# gd32.net
KiCad netlist of a schematic drawn in EAGLE
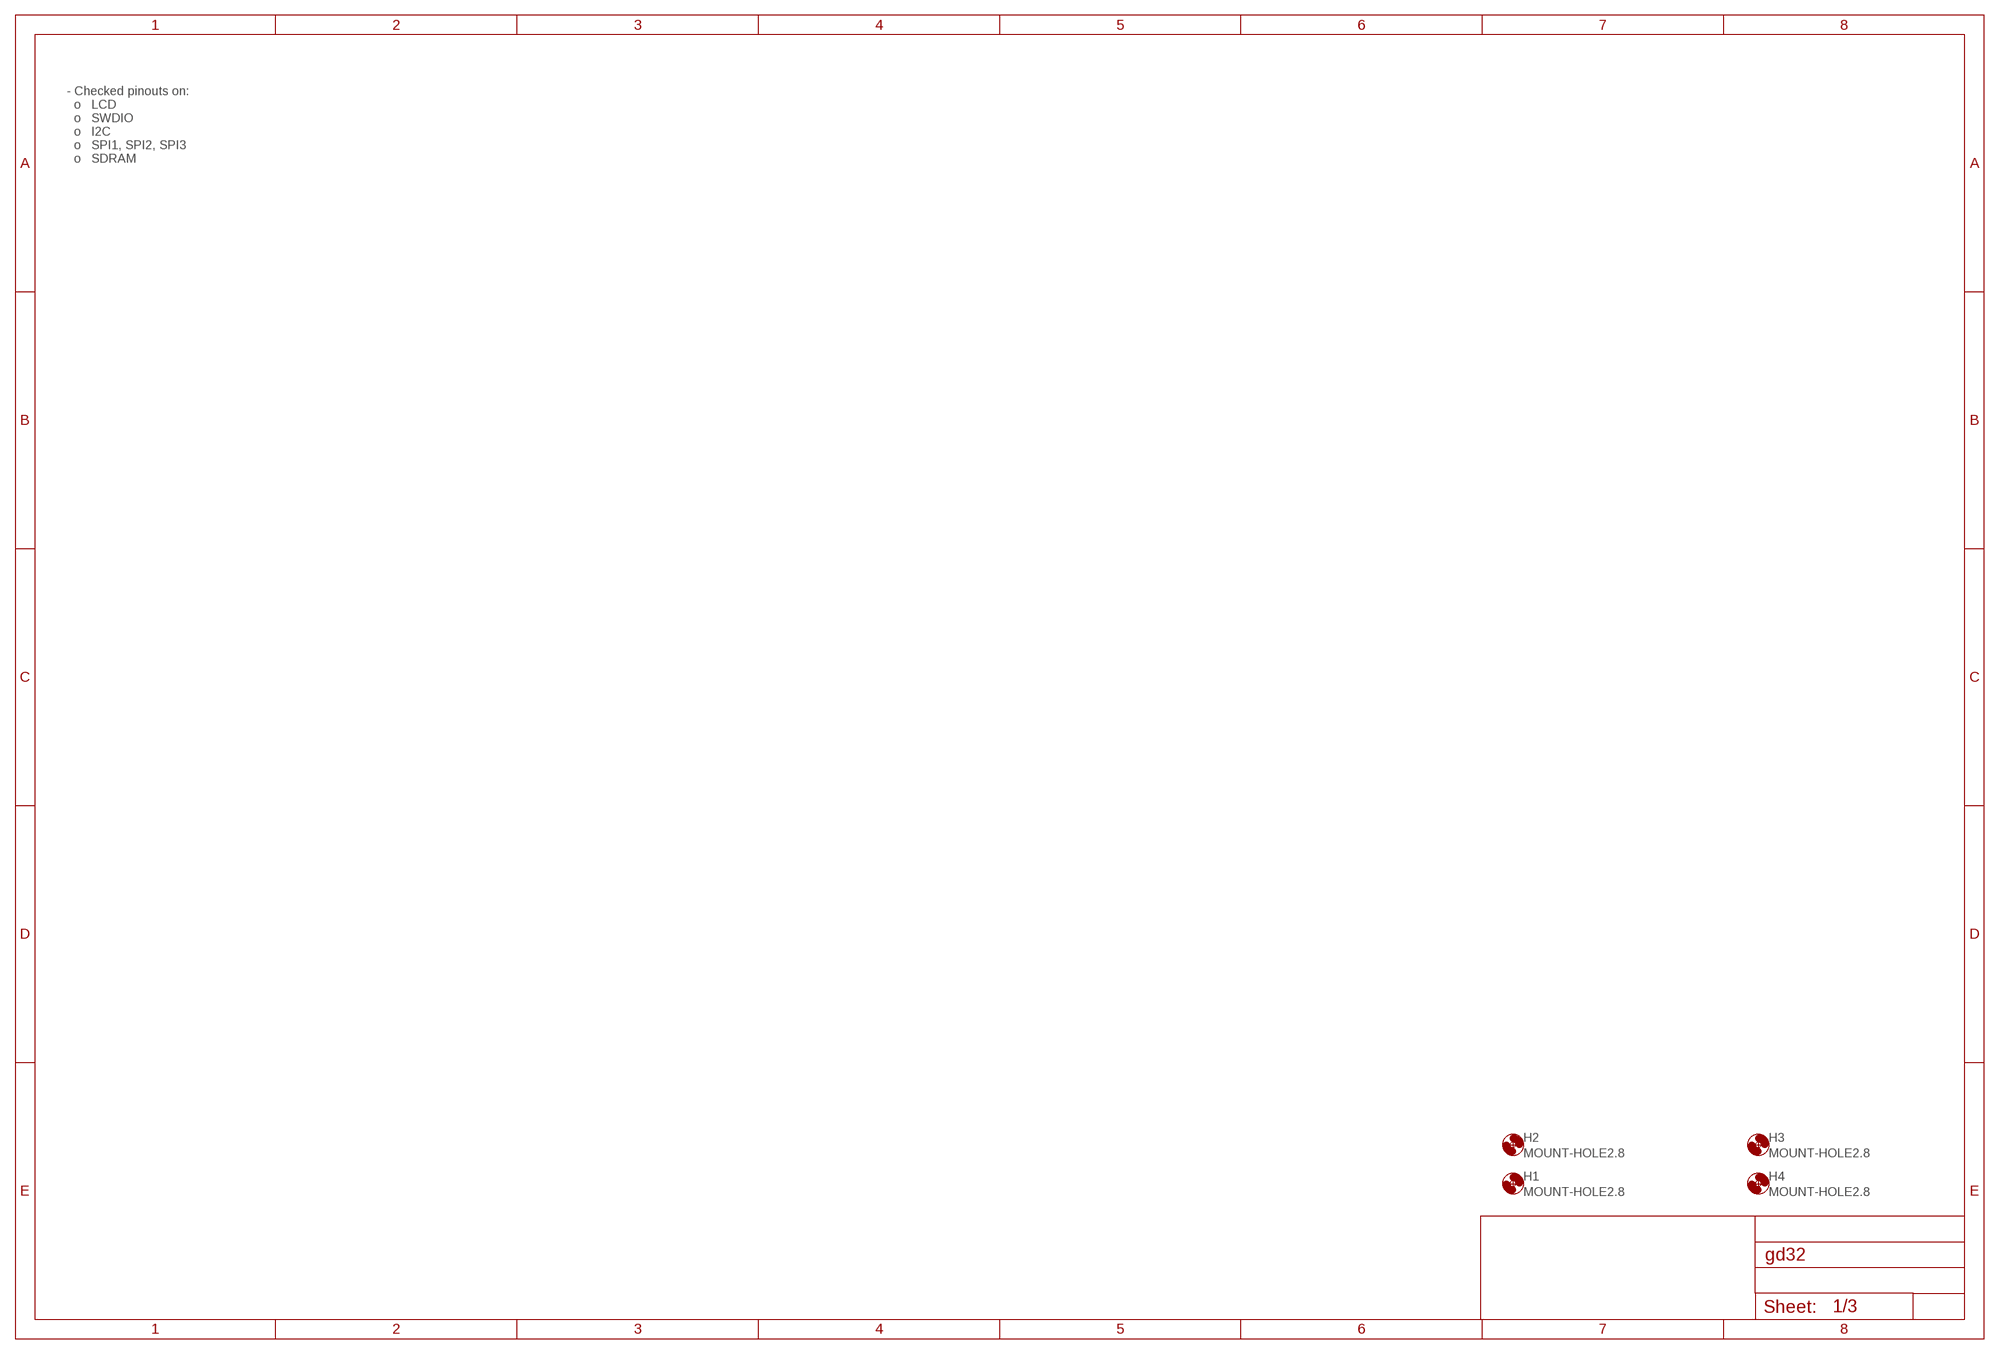
[diagram p0: schematic, sheet 1]
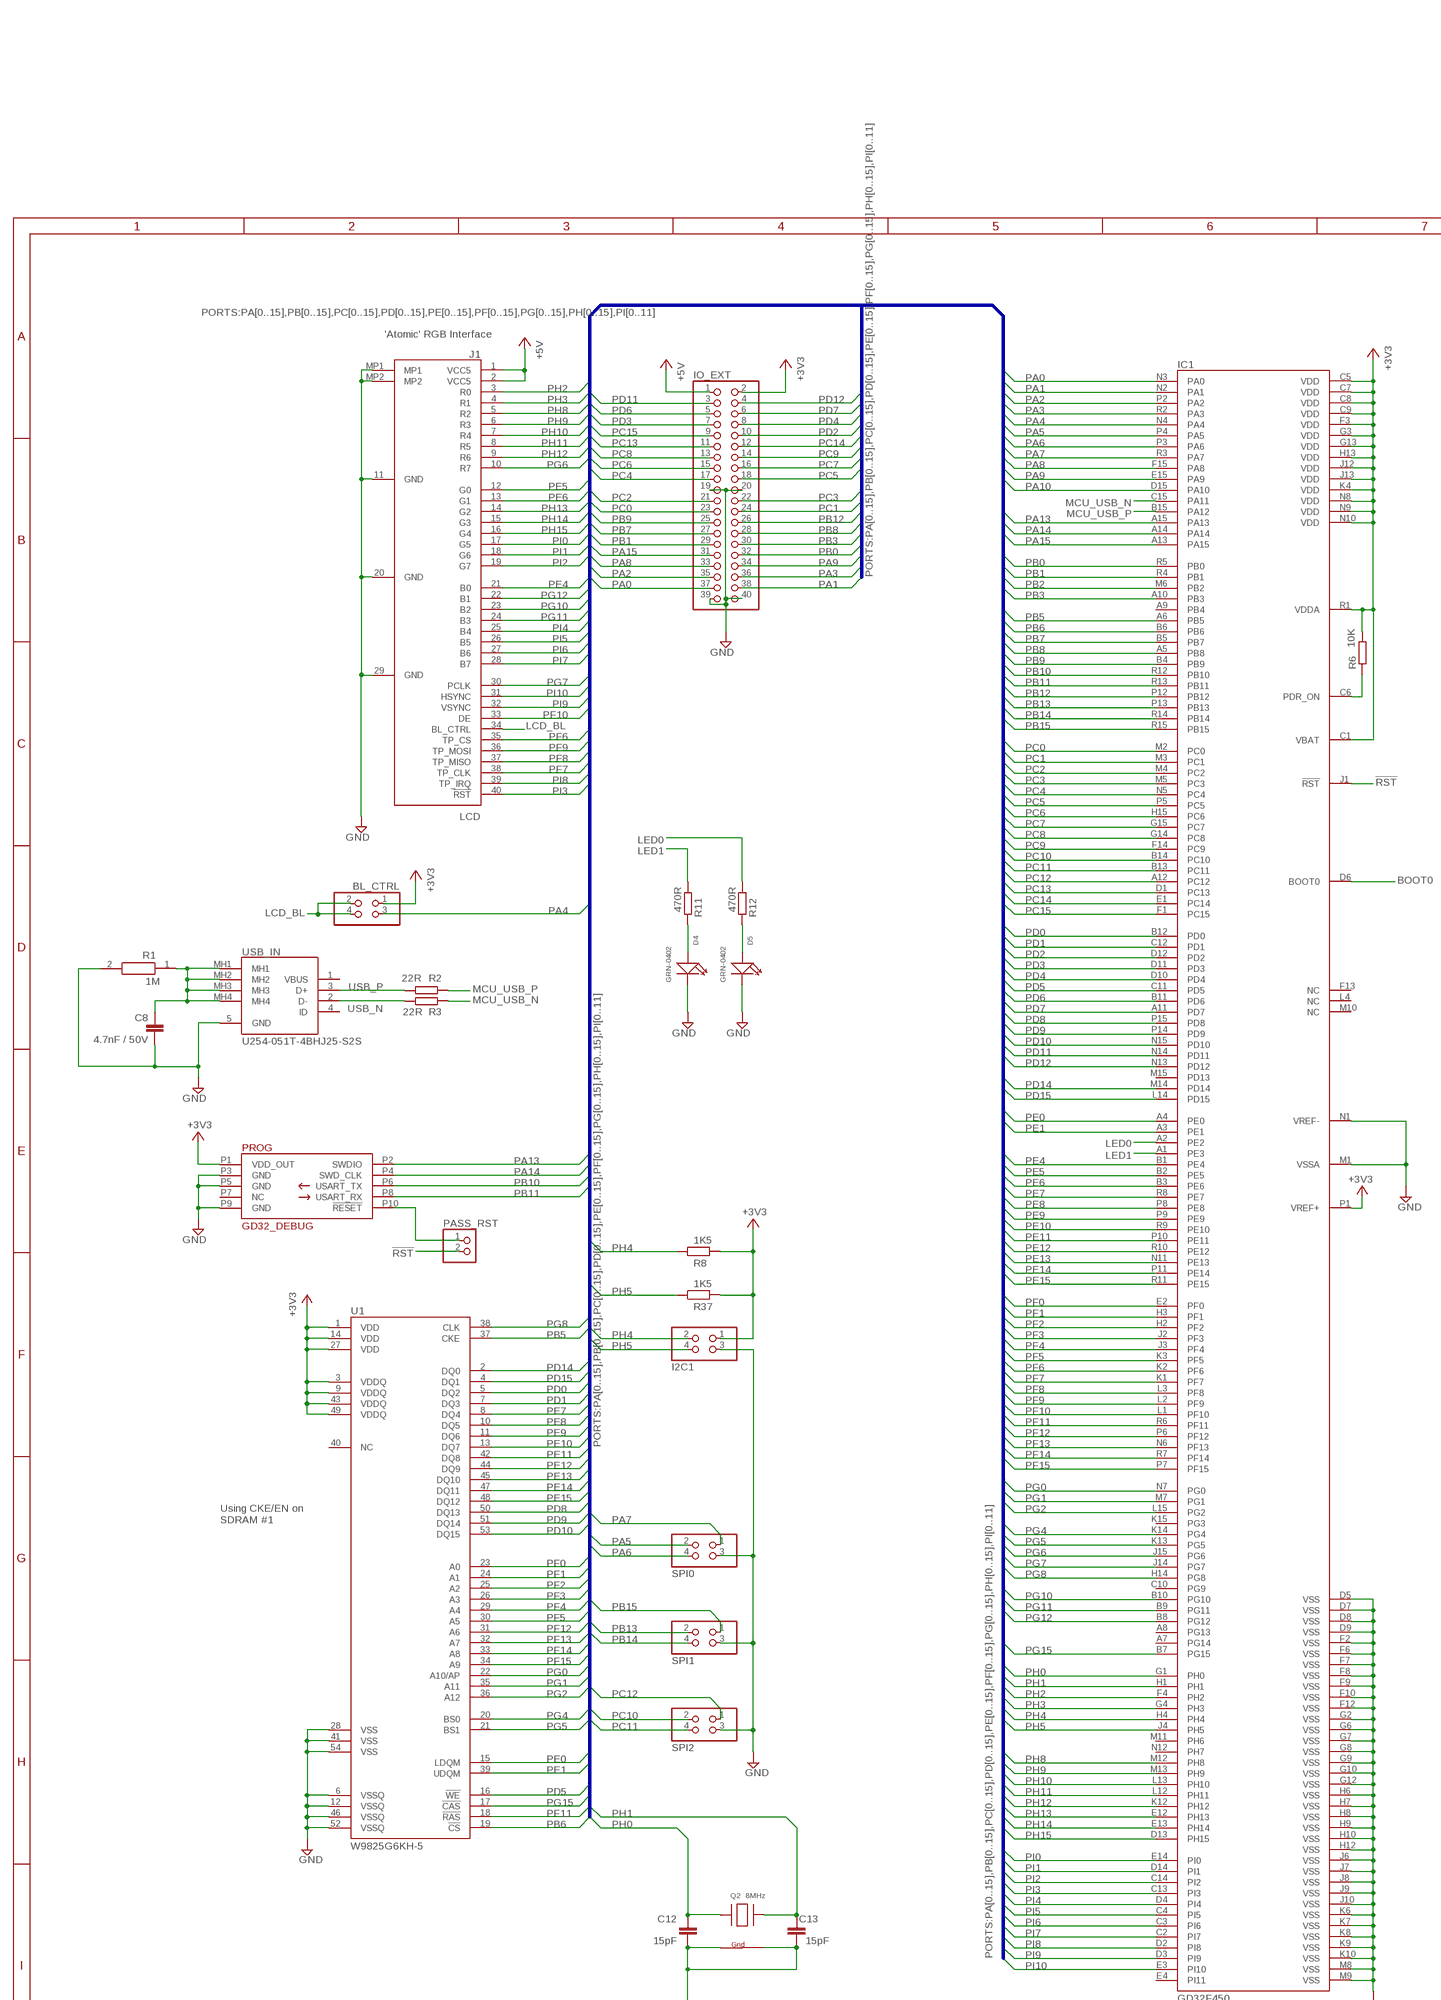
[diagram p1: schematic, sheet 2, part 1 of 3]
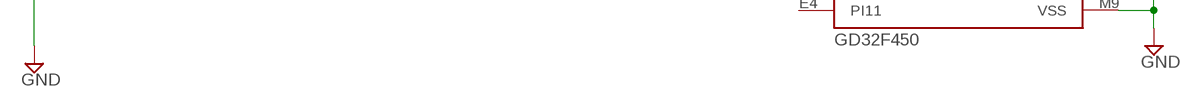
[diagram p2: schematic, sheet 2, part 2 of 3]
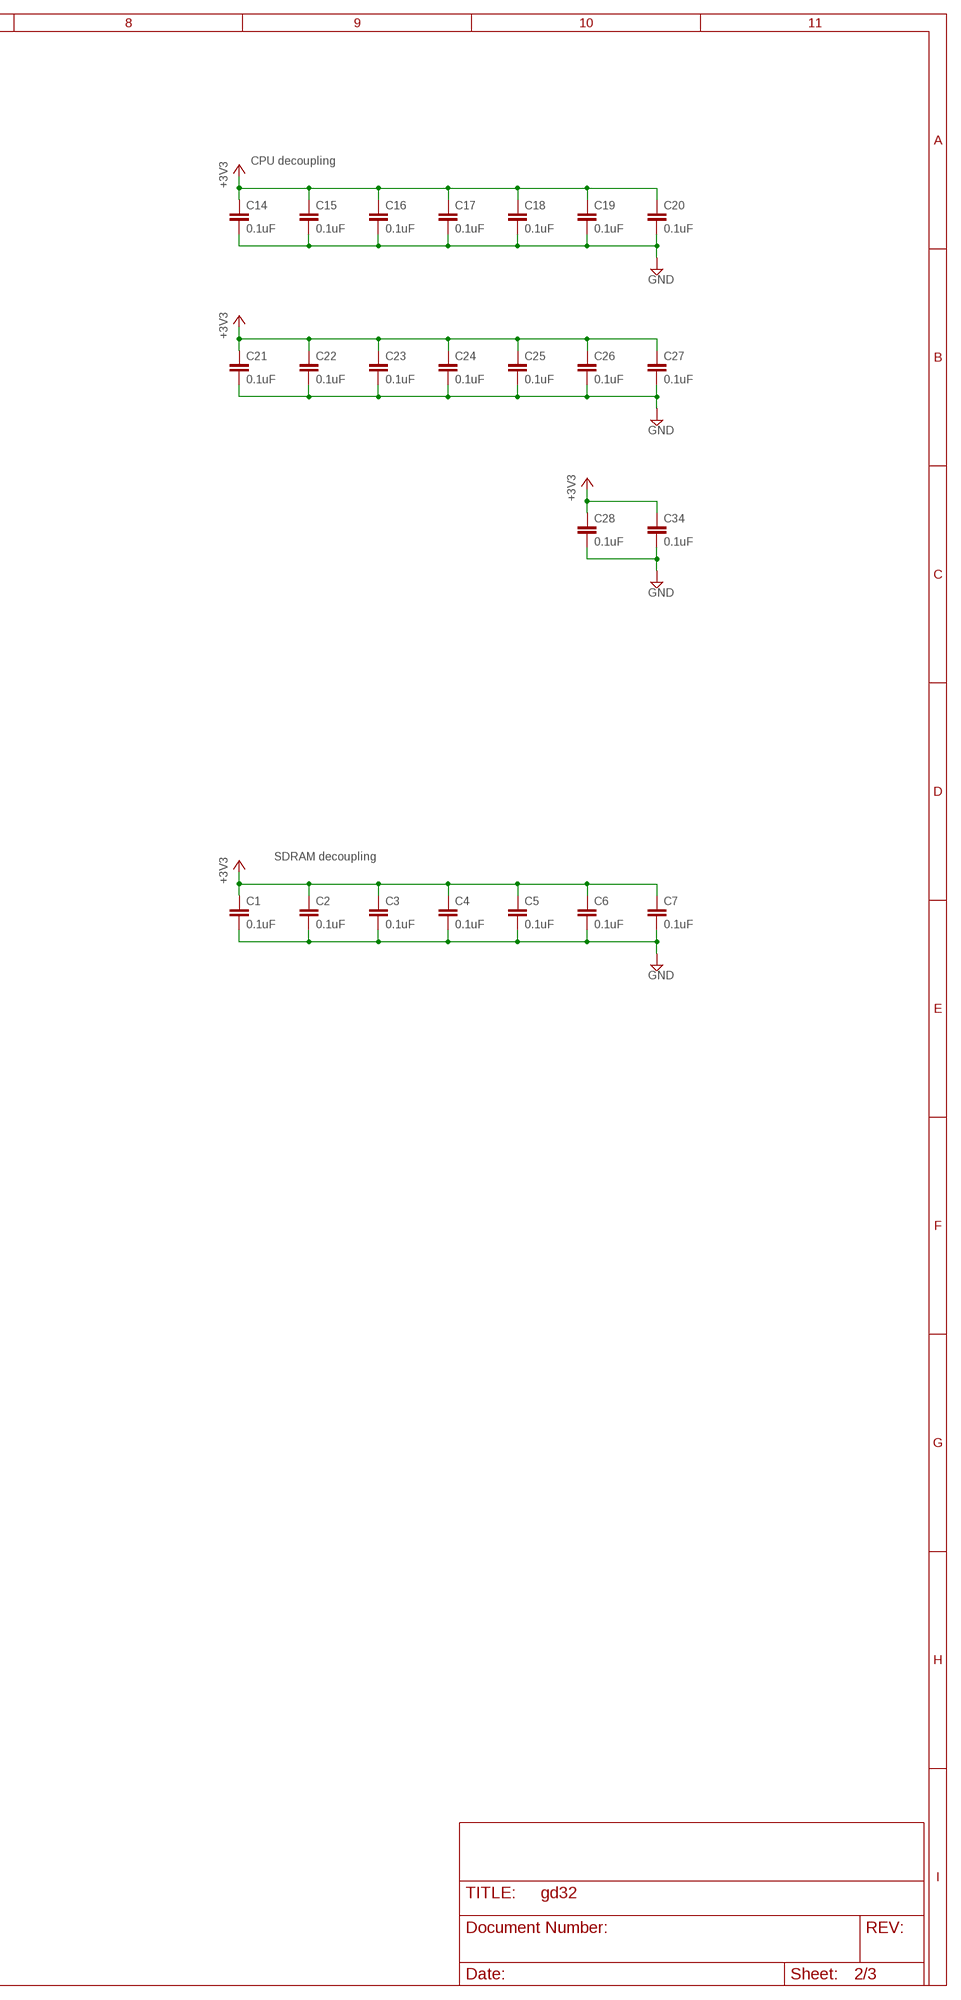
[diagram p3: schematic, sheet 2, part 3 of 3]
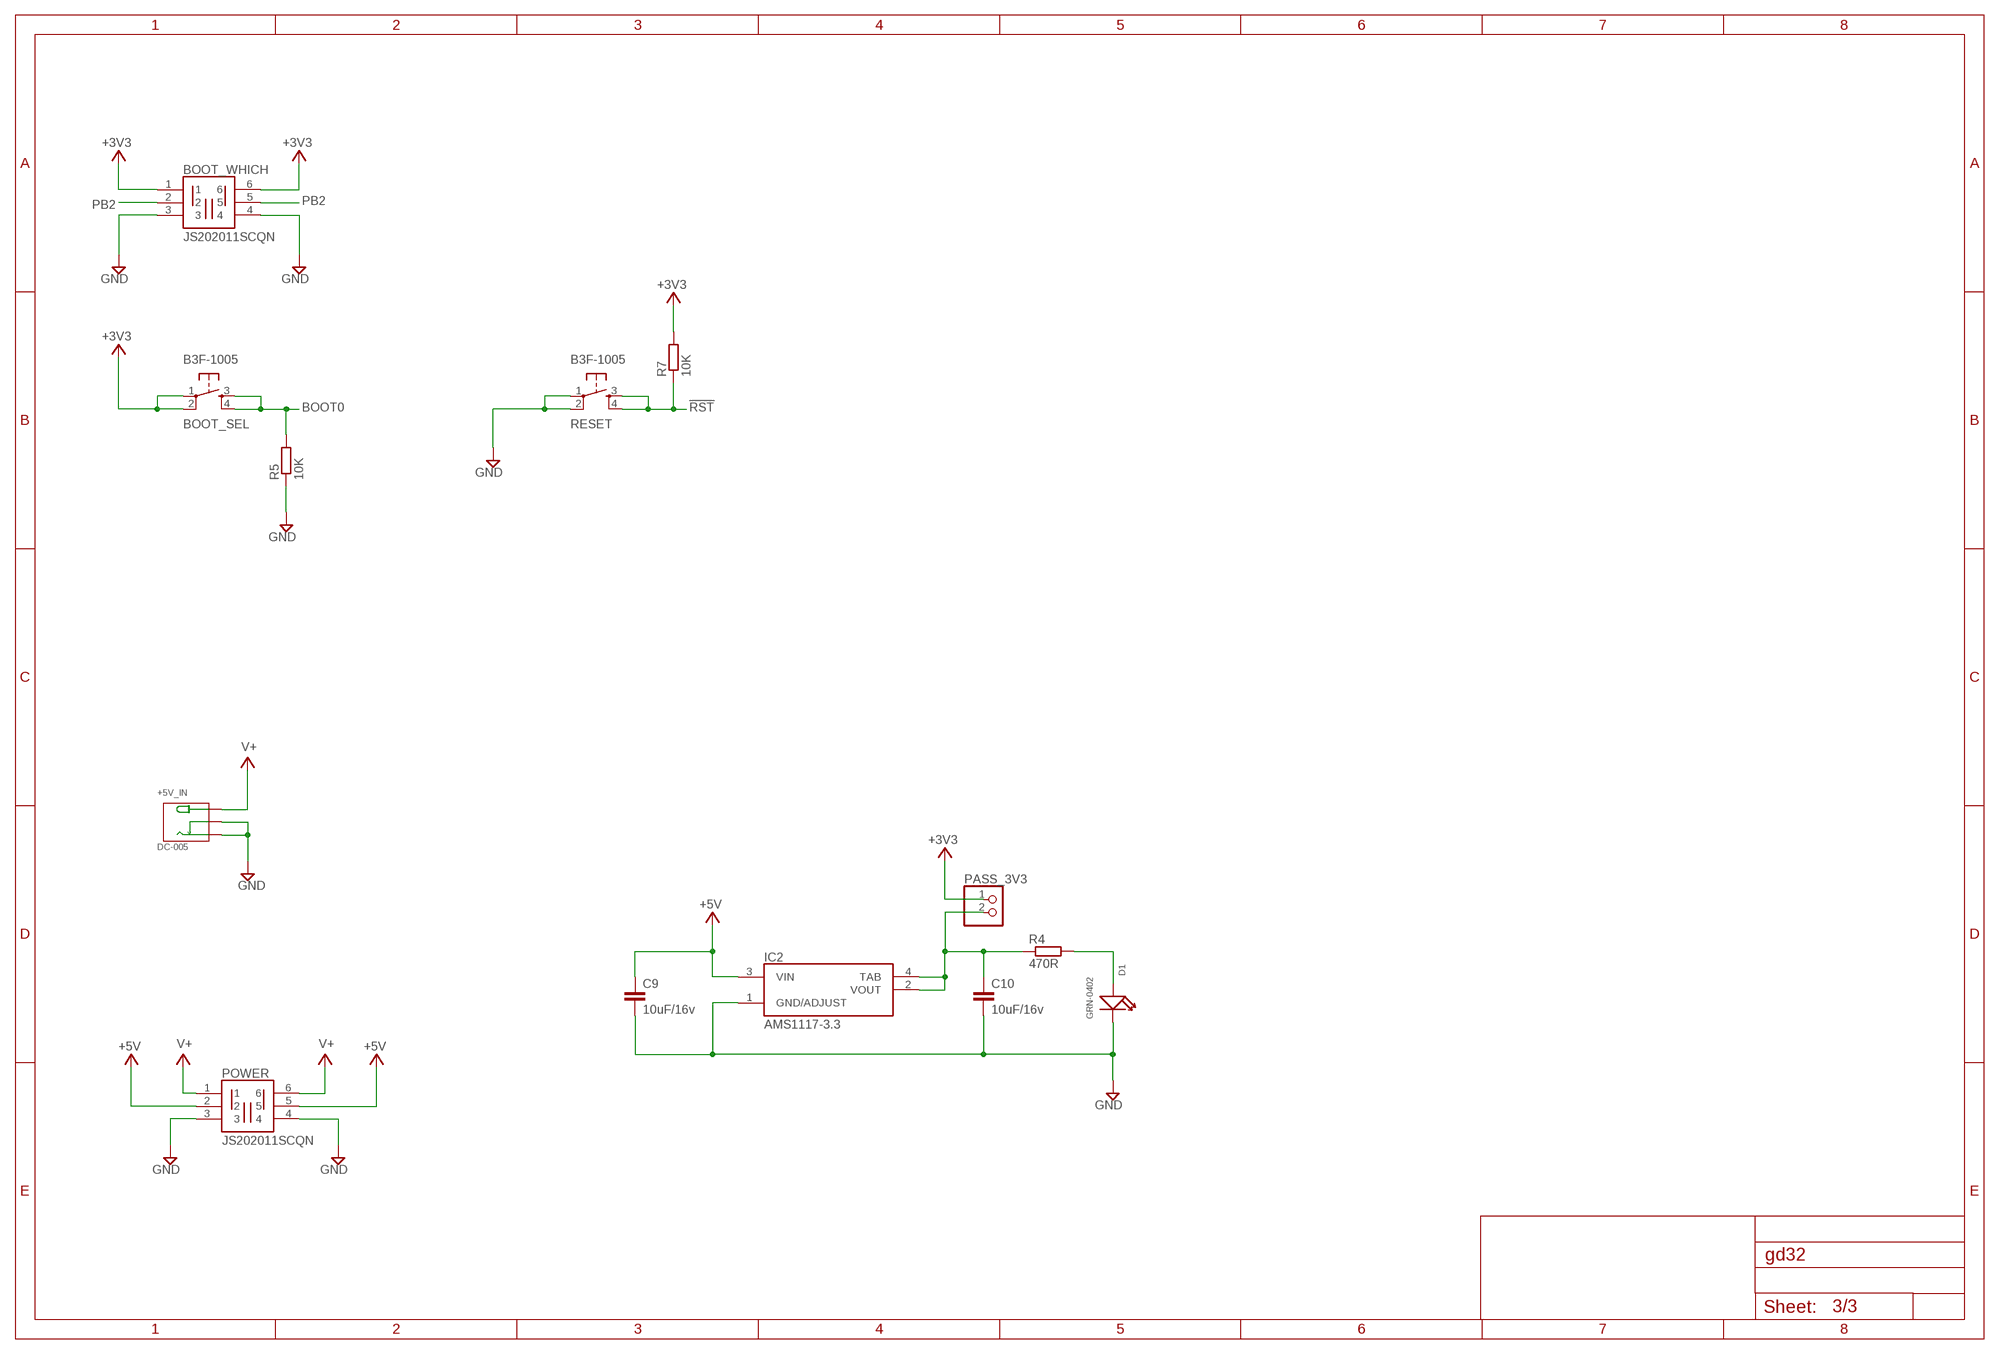
[diagram p4: schematic, sheet 3]

(export (version "E")
  (design (tool "Eeschema 10.0.6"))
  (components
    (comp (ref "+5V_IN")
      (value "DC-005")
      (footprint "eagle-import:DCJ3P-14.2X11.0X9.0MM")
      (libsource (lib "eagle-import") (part "CONN-POWER-JACK-2.1MM(DC-005)"))
    )
    (comp (ref "BOOT_SEL")
      (value "B3F-1005")
      (footprint "eagle-import:TACTILE-PTH")
      (fields (field (name "USE") "B3F-1005"))
      (libsource (lib "eagle-import") (part "TAC_SWITCHPTH"))
    )
    (comp (ref "BOOT_WHICH")
      (value "JS202011SCQN")
      (footprint "eagle-import:JS202011SCQN")
      (fields (field (name "MOUSER_PART_NUMBER") "611-JS202011SCQN"))
      (libsource (lib "eagle-import") (part "JS202011SCQN"))
    )
    (comp (ref "C9")
      (value "10uF/16v")
      (footprint "eagle-import:C0603")
      (libsource (lib "eagle-import") (part "C-EUC0603"))
    )
    (comp (ref "C10")
      (value "10uF/16v")
      (footprint "eagle-import:C0603")
      (libsource (lib "eagle-import") (part "C-EUC0603"))
    )
    (comp (ref "D1")
      (value "GRN-0402")
      (footprint "eagle-import:LED-0402")
      (fields (field (name "MPN") "BL-HB337A-AV-TRB"))
      (libsource (lib "eagle-import") (part "SMD-LED-CLEAR-BLUE(0402)"))
    )
    (comp (ref "IC2")
      (value "AMS1117-3.3")
      (footprint "eagle-import:SOT229P700X180-4N")
      (fields (field (name "MANUFACTURER_PART_NUMBER") "AMS1117-1.5"))
      (libsource (lib "eagle-import") (part "AMS1117-1.5"))
    )
    (comp (ref "PASS_3V3")
      (value "PINHD-1X2")
      (footprint "eagle-import:1X02")
      (libsource (lib "eagle-import") (part "PINHD-1X2"))
    )
    (comp (ref "POWER")
      (value "JS202011SCQN")
      (footprint "eagle-import:JS202011SCQN")
      (fields (field (name "MOUSER_PART_NUMBER") "611-JS202011SCQN"))
      (libsource (lib "eagle-import") (part "JS202011SCQN"))
    )
    (comp (ref "R4")
      (value "470R")
      (footprint "eagle-import:R0402")
      (libsource (lib "eagle-import") (part "R-EU_R0402"))
    )
    (comp (ref "R5")
      (value "10K")
      (footprint "eagle-import:R0402")
      (libsource (lib "eagle-import") (part "R-EU_R0402"))
    )
    (comp (ref "R7")
      (value "10K")
      (footprint "eagle-import:R0402")
      (libsource (lib "eagle-import") (part "R-EU_R0402"))
    )
    (comp (ref "RESET")
      (value "B3F-1005")
      (footprint "eagle-import:TACTILE-PTH")
      (fields (field (name "USE") "B3F-1005"))
      (libsource (lib "eagle-import") (part "TAC_SWITCHPTH"))
    )
    (comp (ref "BL_CTRL")
      (value "PINHD-2X2")
      (footprint "eagle-import:2X02")
      (libsource (lib "eagle-import") (part "PINHD-2X2"))
    )
    (comp (ref "C1")
      (value "0.1uF")
      (footprint "eagle-import:C0201")
      (libsource (lib "eagle-import") (part "C-EUC0201"))
    )
    (comp (ref "C2")
      (value "0.1uF")
      (footprint "eagle-import:C0201")
      (libsource (lib "eagle-import") (part "C-EUC0201"))
    )
    (comp (ref "C3")
      (value "0.1uF")
      (footprint "eagle-import:C0201")
      (libsource (lib "eagle-import") (part "C-EUC0201"))
    )
    (comp (ref "C4")
      (value "0.1uF")
      (footprint "eagle-import:C0201")
      (libsource (lib "eagle-import") (part "C-EUC0201"))
    )
    (comp (ref "C5")
      (value "0.1uF")
      (footprint "eagle-import:C0201")
      (libsource (lib "eagle-import") (part "C-EUC0201"))
    )
    (comp (ref "C6")
      (value "0.1uF")
      (footprint "eagle-import:C0201")
      (libsource (lib "eagle-import") (part "C-EUC0201"))
    )
    (comp (ref "C7")
      (value "0.1uF")
      (footprint "eagle-import:C0201")
      (libsource (lib "eagle-import") (part "C-EUC0201"))
    )
    (comp (ref "C8")
      (value "4.7nF / 50V")
      (footprint "eagle-import:C0201")
      (libsource (lib "eagle-import") (part "C-EUC0201"))
    )
    (comp (ref "C12")
      (value "15pF")
      (footprint "eagle-import:C0201")
      (libsource (lib "eagle-import") (part "C-EUC0201"))
    )
    (comp (ref "C13")
      (value "15pF")
      (footprint "eagle-import:C0201")
      (libsource (lib "eagle-import") (part "C-EUC0201"))
    )
    (comp (ref "C14")
      (value "0.1uF")
      (footprint "eagle-import:C0201")
      (libsource (lib "eagle-import") (part "C-EUC0201"))
    )
    (comp (ref "C15")
      (value "0.1uF")
      (footprint "eagle-import:C0201")
      (libsource (lib "eagle-import") (part "C-EUC0201"))
    )
    (comp (ref "C16")
      (value "0.1uF")
      (footprint "eagle-import:C0201")
      (libsource (lib "eagle-import") (part "C-EUC0201"))
    )
    (comp (ref "C17")
      (value "0.1uF")
      (footprint "eagle-import:C0201")
      (libsource (lib "eagle-import") (part "C-EUC0201"))
    )
    (comp (ref "C18")
      (value "0.1uF")
      (footprint "eagle-import:C0201")
      (libsource (lib "eagle-import") (part "C-EUC0201"))
    )
    (comp (ref "C19")
      (value "0.1uF")
      (footprint "eagle-import:C0201")
      (libsource (lib "eagle-import") (part "C-EUC0201"))
    )
    (comp (ref "C20")
      (value "0.1uF")
      (footprint "eagle-import:C0201")
      (libsource (lib "eagle-import") (part "C-EUC0201"))
    )
    (comp (ref "C21")
      (value "0.1uF")
      (footprint "eagle-import:C0201")
      (libsource (lib "eagle-import") (part "C-EUC0201"))
    )
    (comp (ref "C22")
      (value "0.1uF")
      (footprint "eagle-import:C0201")
      (libsource (lib "eagle-import") (part "C-EUC0201"))
    )
    (comp (ref "C23")
      (value "0.1uF")
      (footprint "eagle-import:C0201")
      (libsource (lib "eagle-import") (part "C-EUC0201"))
    )
    (comp (ref "C24")
      (value "0.1uF")
      (footprint "eagle-import:C0201")
      (libsource (lib "eagle-import") (part "C-EUC0201"))
    )
    (comp (ref "C25")
      (value "0.1uF")
      (footprint "eagle-import:C0201")
      (libsource (lib "eagle-import") (part "C-EUC0201"))
    )
    (comp (ref "C26")
      (value "0.1uF")
      (footprint "eagle-import:C0201")
      (libsource (lib "eagle-import") (part "C-EUC0201"))
    )
    (comp (ref "C27")
      (value "0.1uF")
      (footprint "eagle-import:C0201")
      (libsource (lib "eagle-import") (part "C-EUC0201"))
    )
    (comp (ref "C28")
      (value "0.1uF")
      (footprint "eagle-import:C0201")
      (libsource (lib "eagle-import") (part "C-EUC0201"))
    )
    (comp (ref "C34")
      (value "0.1uF")
      (footprint "eagle-import:C0201")
      (libsource (lib "eagle-import") (part "C-EUC0201"))
    )
    (comp (ref "D4")
      (value "GRN-0402")
      (footprint "eagle-import:LED-0402")
      (fields (field (name "MPN") "BL-HB337A-AV-TRB"))
      (libsource (lib "eagle-import") (part "SMD-LED-CLEAR-BLUE(0402)"))
    )
    (comp (ref "D5")
      (value "GRN-0402")
      (footprint "eagle-import:LED-0402")
      (fields (field (name "MPN") "BL-HB337A-AV-TRB"))
      (libsource (lib "eagle-import") (part "SMD-LED-CLEAR-BLUE(0402)"))
    )
    (comp (ref "I2C1")
      (value "PINHD-2X2")
      (footprint "eagle-import:2X02")
      (libsource (lib "eagle-import") (part "PINHD-2X2"))
    )
    (comp (ref "IC1")
      (value "GD32F450")
      (footprint "eagle-import:BGA201C65P15X15_1000X1000X84")
      (fields (field (name "MANUFACTURER_PART_NUMBER") "GD32F450IKH6"))
      (libsource (lib "eagle-import") (part "GD32F450II"))
    )
    (comp (ref "IO_EXT")
      (value "PINHD-2X20")
      (footprint "eagle-import:2X20")
      (libsource (lib "eagle-import") (part "PINHD-2X20"))
    )
    (comp (ref "J1")
      (value "LCD")
      (footprint "eagle-import:CF5040FD0R005NH")
      (fields (field (name "MANUFACTURER_PART_NUMBER") "CF5040FD0R0-05-NH"))
      (libsource (lib "eagle-import") (part "CF5040FD0R0-05-NH"))
    )
    (comp (ref "PASS_RST")
      (value "PINHD-1X2")
      (footprint "eagle-import:1X02")
      (libsource (lib "eagle-import") (part "PINHD-1X2"))
    )
    (comp (ref "PROG")
      (value "GD32_DEBUG")
      (footprint "eagle-import:SWD_DEBUG")
      (libsource (lib "eagle-import") (part "GD32_DEBUG"))
    )
    (comp (ref "Q2")
      (value "8MHz")
      (footprint "eagle-import:NX3225")
      (libsource (lib "eagle-import") (part "XTAL-4-3225"))
    )
    (comp (ref "R1")
      (value "1M")
      (footprint "eagle-import:ERJ1GN_(0201)")
      (fields
        (field (name "ARROW_PART_NUMBER") "ERJ-1GNF1004C")
        (field (name "MOUSER_PART_NUMBER") "667-ERJ-1GNF1004C")
      )
      (libsource (lib "eagle-import") (part "ERJ-1GNF1004C"))
    )
    (comp (ref "R2")
      (value "22R")
      (footprint "eagle-import:R0402")
      (libsource (lib "eagle-import") (part "R-EU_R0402"))
    )
    (comp (ref "R3")
      (value "22R")
      (footprint "eagle-import:R0402")
      (libsource (lib "eagle-import") (part "R-EU_R0402"))
    )
    (comp (ref "R6")
      (value "10K")
      (footprint "eagle-import:R0402")
      (libsource (lib "eagle-import") (part "R-EU_R0402"))
    )
    (comp (ref "R8")
      (value "1K5")
      (footprint "eagle-import:R0603")
      (libsource (lib "eagle-import") (part "R-EU_R0603"))
    )
    (comp (ref "R11")
      (value "470R")
      (footprint "eagle-import:R0402")
      (libsource (lib "eagle-import") (part "R-EU_R0402"))
    )
    (comp (ref "R12")
      (value "470R")
      (footprint "eagle-import:R0402")
      (libsource (lib "eagle-import") (part "R-EU_R0402"))
    )
    (comp (ref "R37")
      (value "1K5")
      (footprint "eagle-import:R0603")
      (libsource (lib "eagle-import") (part "R-EU_R0603"))
    )
    (comp (ref "SPI0")
      (value "PINHD-2X2")
      (footprint "eagle-import:2X02")
      (libsource (lib "eagle-import") (part "PINHD-2X2"))
    )
    (comp (ref "SPI1")
      (value "PINHD-2X2")
      (footprint "eagle-import:2X02")
      (libsource (lib "eagle-import") (part "PINHD-2X2"))
    )
    (comp (ref "SPI2")
      (value "PINHD-2X2")
      (footprint "eagle-import:2X02")
      (libsource (lib "eagle-import") (part "PINHD-2X2"))
    )
    (comp (ref "U1")
      (value "W9825G6KH-5")
      (footprint "eagle-import:SOP80P1176X120-54N")
      (fields (field (name "MOUSER_PART_NUMBER") "454-W9825G6KH-5"))
      (libsource (lib "eagle-import") (part "W9825G6KH-5"))
    )
    (comp (ref "USB_IN")
      (value "U254-051T-4BHJ25-S2S")
      (footprint "eagle-import:U254051T4BHJ25S2S")
      (libsource (lib "eagle-import") (part "U254-051T-4BHJ25-S2S"))
    )
    (comp (ref "H1")
      (value "MOUNT-HOLE2.8")
      (footprint "eagle-import:2,8")
      (libsource (lib "eagle-import") (part "MOUNT-HOLE2.8"))
    )
    (comp (ref "H2")
      (value "MOUNT-HOLE2.8")
      (footprint "eagle-import:2,8")
      (libsource (lib "eagle-import") (part "MOUNT-HOLE2.8"))
    )
    (comp (ref "H3")
      (value "MOUNT-HOLE2.8")
      (footprint "eagle-import:2,8")
      (libsource (lib "eagle-import") (part "MOUNT-HOLE2.8"))
    )
    (comp (ref "H4")
      (value "MOUNT-HOLE2.8")
      (footprint "eagle-import:2,8")
      (libsource (lib "eagle-import") (part "MOUNT-HOLE2.8"))
    )
  )
  (nets
    (net (code "1") (name "+3V3") (class "Default")
      (node (ref "BL_CTRL") (pin "1") (pinfunction "1_1") (pintype "passive"))
      (node (ref "BOOT_SEL") (pin "1") (pinfunction "1_1") (pintype "passive"))
      (node (ref "BOOT_SEL") (pin "2") (pinfunction "2_2") (pintype "passive"))
      (node (ref "BOOT_WHICH") (pin "1") (pinfunction "1_1") (pintype "bidirectional"))
      (node (ref "BOOT_WHICH") (pin "6") (pinfunction "6_6") (pintype "bidirectional"))
      (node (ref "C1") (pin "1") (pinfunction "1_1") (pintype "passive"))
      (node (ref "C14") (pin "1") (pinfunction "1_1") (pintype "passive"))
      (node (ref "C15") (pin "1") (pinfunction "1_1") (pintype "passive"))
      (node (ref "C16") (pin "1") (pinfunction "1_1") (pintype "passive"))
      (node (ref "C17") (pin "1") (pinfunction "1_1") (pintype "passive"))
      (node (ref "C18") (pin "1") (pinfunction "1_1") (pintype "passive"))
      (node (ref "C19") (pin "1") (pinfunction "1_1") (pintype "passive"))
      (node (ref "C2") (pin "1") (pinfunction "1_1") (pintype "passive"))
      (node (ref "C20") (pin "1") (pinfunction "1_1") (pintype "passive"))
      (node (ref "C21") (pin "1") (pinfunction "1_1") (pintype "passive"))
      (node (ref "C22") (pin "1") (pinfunction "1_1") (pintype "passive"))
      (node (ref "C23") (pin "1") (pinfunction "1_1") (pintype "passive"))
      (node (ref "C24") (pin "1") (pinfunction "1_1") (pintype "passive"))
      (node (ref "C25") (pin "1") (pinfunction "1_1") (pintype "passive"))
      (node (ref "C26") (pin "1") (pinfunction "1_1") (pintype "passive"))
      (node (ref "C27") (pin "1") (pinfunction "1_1") (pintype "passive"))
      (node (ref "C28") (pin "1") (pinfunction "1_1") (pintype "passive"))
      (node (ref "C3") (pin "1") (pinfunction "1_1") (pintype "passive"))
      (node (ref "C34") (pin "1") (pinfunction "1_1") (pintype "passive"))
      (node (ref "C4") (pin "1") (pinfunction "1_1") (pintype "passive"))
      (node (ref "C5") (pin "1") (pinfunction "1_1") (pintype "passive"))
      (node (ref "C6") (pin "1") (pinfunction "1_1") (pintype "passive"))
      (node (ref "C7") (pin "1") (pinfunction "1_1") (pintype "passive"))
      (node (ref "I2C1") (pin "1") (pinfunction "1_1") (pintype "passive"))
      (node (ref "IC1") (pin "C1") (pinfunction "VBAT_C1") (pintype "bidirectional"))
      (node (ref "IC1") (pin "C5") (pinfunction "VDD_C5") (pintype "bidirectional"))
      (node (ref "IC1") (pin "C7") (pinfunction "VDD_C7") (pintype "bidirectional"))
      (node (ref "IC1") (pin "C8") (pinfunction "VDD_C8") (pintype "bidirectional"))
      (node (ref "IC1") (pin "C9") (pinfunction "VDD_C9") (pintype "bidirectional"))
      (node (ref "IC1") (pin "F3") (pinfunction "VDD_F3") (pintype "bidirectional"))
      (node (ref "IC1") (pin "G13") (pinfunction "VDD_G13") (pintype "bidirectional"))
      (node (ref "IC1") (pin "G3") (pinfunction "VDD_G3") (pintype "bidirectional"))
      (node (ref "IC1") (pin "H13") (pinfunction "VDD_H13") (pintype "bidirectional"))
      (node (ref "IC1") (pin "J12") (pinfunction "VDD_J12") (pintype "bidirectional"))
      (node (ref "IC1") (pin "J13") (pinfunction "VDD_J13") (pintype "bidirectional"))
      (node (ref "IC1") (pin "K4") (pinfunction "VDD_K4") (pintype "bidirectional"))
      (node (ref "IC1") (pin "N10") (pinfunction "VDD_N10") (pintype "bidirectional"))
      (node (ref "IC1") (pin "N8") (pinfunction "VDD_N8") (pintype "bidirectional"))
      (node (ref "IC1") (pin "N9") (pinfunction "VDD_N9") (pintype "bidirectional"))
      (node (ref "IC1") (pin "P1") (pinfunction "VREF+_P1") (pintype "bidirectional"))
      (node (ref "IC1") (pin "R1") (pinfunction "VDDA_R1") (pintype "bidirectional"))
      (node (ref "IO_EXT") (pin "2") (pinfunction "2_2") (pintype "passive"))
      (node (ref "PASS_3V3") (pin "1") (pinfunction "1_1") (pintype "passive"))
      (node (ref "PROG") (pin "P1") (pinfunction "VDD_OUT_P1") (pintype "bidirectional"))
      (node (ref "R37") (pin "2") (pinfunction "2_2") (pintype "passive"))
      (node (ref "R6") (pin "2") (pinfunction "2_2") (pintype "passive"))
      (node (ref "R7") (pin "2") (pinfunction "2_2") (pintype "passive"))
      (node (ref "R8") (pin "2") (pinfunction "2_2") (pintype "passive"))
      (node (ref "U1") (pin "1") (pinfunction "VDD_1") (pintype "bidirectional"))
      (node (ref "U1") (pin "14") (pinfunction "VDD_14") (pintype "bidirectional"))
      (node (ref "U1") (pin "27") (pinfunction "VDD_27") (pintype "bidirectional"))
      (node (ref "U1") (pin "3") (pinfunction "VDDQ_3") (pintype "bidirectional"))
      (node (ref "U1") (pin "43") (pinfunction "VDDQ_43") (pintype "bidirectional"))
      (node (ref "U1") (pin "49") (pinfunction "VDDQ_49") (pintype "bidirectional"))
      (node (ref "U1") (pin "9") (pinfunction "VDDQ_9") (pintype "bidirectional"))
    )
    (net (code "2") (name "+5V") (class "Default")
      (node (ref "C9") (pin "1") (pinfunction "1_1") (pintype "passive"))
      (node (ref "IC2") (pin "3") (pinfunction "VIN_3") (pintype "bidirectional"))
      (node (ref "IO_EXT") (pin "1") (pinfunction "1_1") (pintype "passive"))
      (node (ref "J1") (pin "1") (pinfunction "VCC5_1") (pintype "bidirectional"))
      (node (ref "J1") (pin "2") (pinfunction "VCC5_2") (pintype "bidirectional"))
      (node (ref "POWER") (pin "2") (pinfunction "2_2") (pintype "bidirectional"))
      (node (ref "POWER") (pin "5") (pinfunction "5_5") (pintype "bidirectional"))
    )
    (net (code "4") (name "BOOT0") (class "Default")
      (node (ref "BOOT_SEL") (pin "3") (pinfunction "3_3") (pintype "passive"))
      (node (ref "BOOT_SEL") (pin "4") (pinfunction "4_4") (pintype "passive"))
      (node (ref "IC1") (pin "D6") (pinfunction "BOOT0_D6") (pintype "bidirectional"))
      (node (ref "R5") (pin "2") (pinfunction "2_2") (pintype "passive"))
    )
    (net (code "5") (name "GND") (class "Default")
      (node (ref "+5V_IN") (pin "-1") (pinfunction "-_-1") (pintype "bidirectional"))
      (node (ref "+5V_IN") (pin "-2") (pinfunction "CDN_-2") (pintype "bidirectional"))
      (node (ref "BOOT_WHICH") (pin "3") (pinfunction "3_3") (pintype "bidirectional"))
      (node (ref "BOOT_WHICH") (pin "4") (pinfunction "4_4") (pintype "bidirectional"))
      (node (ref "C1") (pin "2") (pinfunction "2_2") (pintype "passive"))
      (node (ref "C10") (pin "2") (pinfunction "2_2") (pintype "passive"))
      (node (ref "C12") (pin "2") (pinfunction "2_2") (pintype "passive"))
      (node (ref "C13") (pin "2") (pinfunction "2_2") (pintype "passive"))
      (node (ref "C14") (pin "2") (pinfunction "2_2") (pintype "passive"))
      (node (ref "C15") (pin "2") (pinfunction "2_2") (pintype "passive"))
      (node (ref "C16") (pin "2") (pinfunction "2_2") (pintype "passive"))
      (node (ref "C17") (pin "2") (pinfunction "2_2") (pintype "passive"))
      (node (ref "C18") (pin "2") (pinfunction "2_2") (pintype "passive"))
      (node (ref "C19") (pin "2") (pinfunction "2_2") (pintype "passive"))
      (node (ref "C2") (pin "2") (pinfunction "2_2") (pintype "passive"))
      (node (ref "C20") (pin "2") (pinfunction "2_2") (pintype "passive"))
      (node (ref "C21") (pin "2") (pinfunction "2_2") (pintype "passive"))
      (node (ref "C22") (pin "2") (pinfunction "2_2") (pintype "passive"))
      (node (ref "C23") (pin "2") (pinfunction "2_2") (pintype "passive"))
      (node (ref "C24") (pin "2") (pinfunction "2_2") (pintype "passive"))
      (node (ref "C25") (pin "2") (pinfunction "2_2") (pintype "passive"))
      (node (ref "C26") (pin "2") (pinfunction "2_2") (pintype "passive"))
      (node (ref "C27") (pin "2") (pinfunction "2_2") (pintype "passive"))
      (node (ref "C28") (pin "2") (pinfunction "2_2") (pintype "passive"))
      (node (ref "C3") (pin "2") (pinfunction "2_2") (pintype "passive"))
      (node (ref "C34") (pin "2") (pinfunction "2_2") (pintype "passive"))
      (node (ref "C4") (pin "2") (pinfunction "2_2") (pintype "passive"))
      (node (ref "C5") (pin "2") (pinfunction "2_2") (pintype "passive"))
      (node (ref "C6") (pin "2") (pinfunction "2_2") (pintype "passive"))
      (node (ref "C7") (pin "2") (pinfunction "2_2") (pintype "passive"))
      (node (ref "C8") (pin "2") (pinfunction "2_2") (pintype "passive"))
      (node (ref "C9") (pin "2") (pinfunction "2_2") (pintype "passive"))
      (node (ref "D1") (pin "-") (pinfunction "-_-") (pintype "passive"))
      (node (ref "D4") (pin "-") (pinfunction "-_-") (pintype "passive"))
      (node (ref "D5") (pin "-") (pinfunction "-_-") (pintype "passive"))
      (node (ref "I2C1") (pin "3") (pinfunction "3_3") (pintype "passive"))
      (node (ref "IC1") (pin "D5") (pinfunction "VSS_D5") (pintype "bidirectional"))
      (node (ref "IC1") (pin "D7") (pinfunction "VSS_D7") (pintype "bidirectional"))
      (node (ref "IC1") (pin "D8") (pinfunction "VSS_D8") (pintype "bidirectional"))
      (node (ref "IC1") (pin "D9") (pinfunction "VSS_D9") (pintype "bidirectional"))
      (node (ref "IC1") (pin "F10") (pinfunction "VSS_F10") (pintype "bidirectional"))
      (node (ref "IC1") (pin "F12") (pinfunction "VSS_F12") (pintype "bidirectional"))
      (node (ref "IC1") (pin "F2") (pinfunction "VSS_F2") (pintype "bidirectional"))
      (node (ref "IC1") (pin "F6") (pinfunction "VSS_F6") (pintype "bidirectional"))
      (node (ref "IC1") (pin "F7") (pinfunction "VSS_F7") (pintype "bidirectional"))
      (node (ref "IC1") (pin "F8") (pinfunction "VSS_F8") (pintype "bidirectional"))
      (node (ref "IC1") (pin "F9") (pinfunction "VSS_F9") (pintype "bidirectional"))
      (node (ref "IC1") (pin "G10") (pinfunction "VSS_G10") (pintype "bidirectional"))
      (node (ref "IC1") (pin "G12") (pinfunction "VSS_G12") (pintype "bidirectional"))
      (node (ref "IC1") (pin "G2") (pinfunction "VSS_G2") (pintype "bidirectional"))
      (node (ref "IC1") (pin "G6") (pinfunction "VSS_G6") (pintype "bidirectional"))
      (node (ref "IC1") (pin "G7") (pinfunction "VSS_G7") (pintype "bidirectional"))
      (node (ref "IC1") (pin "G8") (pinfunction "VSS_G8") (pintype "bidirectional"))
      (node (ref "IC1") (pin "G9") (pinfunction "VSS_G9") (pintype "bidirectional"))
      (node (ref "IC1") (pin "H10") (pinfunction "VSS_H10") (pintype "bidirectional"))
      (node (ref "IC1") (pin "H12") (pinfunction "VSS_H12") (pintype "bidirectional"))
      (node (ref "IC1") (pin "H6") (pinfunction "VSS_H6") (pintype "bidirectional"))
      (node (ref "IC1") (pin "H7") (pinfunction "VSS_H7") (pintype "bidirectional"))
      (node (ref "IC1") (pin "H8") (pinfunction "VSS_H8") (pintype "bidirectional"))
      (node (ref "IC1") (pin "H9") (pinfunction "VSS_H9") (pintype "bidirectional"))
      (node (ref "IC1") (pin "J10") (pinfunction "VSS_J10") (pintype "bidirectional"))
      (node (ref "IC1") (pin "J6") (pinfunction "VSS_J6") (pintype "bidirectional"))
      (node (ref "IC1") (pin "J7") (pinfunction "VSS_J7") (pintype "bidirectional"))
      (node (ref "IC1") (pin "J8") (pinfunction "VSS_J8") (pintype "bidirectional"))
      (node (ref "IC1") (pin "J9") (pinfunction "VSS_J9") (pintype "bidirectional"))
      (node (ref "IC1") (pin "K10") (pinfunction "VSS_K10") (pintype "bidirectional"))
      (node (ref "IC1") (pin "K6") (pinfunction "VSS_K6") (pintype "bidirectional"))
      (node (ref "IC1") (pin "K7") (pinfunction "VSS_K7") (pintype "bidirectional"))
      (node (ref "IC1") (pin "K8") (pinfunction "VSS_K8") (pintype "bidirectional"))
      (node (ref "IC1") (pin "K9") (pinfunction "VSS_K9") (pintype "bidirectional"))
      (node (ref "IC1") (pin "M1") (pinfunction "VSSA_M1") (pintype "bidirectional"))
      (node (ref "IC1") (pin "M8") (pinfunction "VSS_M8") (pintype "bidirectional"))
      (node (ref "IC1") (pin "M9") (pinfunction "VSS_M9") (pintype "bidirectional"))
      (node (ref "IC1") (pin "N1") (pinfunction "VREF-_N1") (pintype "bidirectional"))
      (node (ref "IC2") (pin "1") (pinfunction "GND/ADJUST_1") (pintype "bidirectional"))
      (node (ref "IO_EXT") (pin "19") (pinfunction "19_19") (pintype "passive"))
      (node (ref "IO_EXT") (pin "20") (pinfunction "20_20") (pintype "passive"))
      (node (ref "IO_EXT") (pin "39") (pinfunction "39_39") (pintype "passive"))
      (node (ref "IO_EXT") (pin "40") (pinfunction "40_40") (pintype "passive"))
      (node (ref "J1") (pin "11") (pinfunction "GND_11") (pintype "bidirectional"))
      (node (ref "J1") (pin "20") (pinfunction "GND_20") (pintype "bidirectional"))
      (node (ref "J1") (pin "29") (pinfunction "GND_29") (pintype "bidirectional"))
      (node (ref "J1") (pin "MP1") (pinfunction "MP1_MP1") (pintype "bidirectional"))
      (node (ref "J1") (pin "MP2") (pinfunction "MP2_MP2") (pintype "bidirectional"))
      (node (ref "POWER") (pin "3") (pinfunction "3_3") (pintype "bidirectional"))
      (node (ref "POWER") (pin "4") (pinfunction "4_4") (pintype "bidirectional"))
      (node (ref "PROG") (pin "P3") (pinfunction "GND_P3") (pintype "bidirectional"))
      (node (ref "PROG") (pin "P5") (pinfunction "GND_P5") (pintype "bidirectional"))
      (node (ref "PROG") (pin "P9") (pinfunction "GND_P9") (pintype "bidirectional"))
      (node (ref "Q2") (pin "2") (pinfunction "G2_2") (pintype "power_in"))
      (node (ref "Q2") (pin "4") (pinfunction "G1_4") (pintype "power_in"))
      (node (ref "R1") (pin "2") (pinfunction "2_2") (pintype "bidirectional"))
      (node (ref "R5") (pin "1") (pinfunction "1_1") (pintype "passive"))
      (node (ref "RESET") (pin "1") (pinfunction "1_1") (pintype "passive"))
      (node (ref "RESET") (pin "2") (pinfunction "2_2") (pintype "passive"))
      (node (ref "SPI0") (pin "3") (pinfunction "3_3") (pintype "passive"))
      (node (ref "SPI1") (pin "3") (pinfunction "3_3") (pintype "passive"))
      (node (ref "SPI2") (pin "3") (pinfunction "3_3") (pintype "passive"))
      (node (ref "U1") (pin "12") (pinfunction "VSSQ_12") (pintype "bidirectional"))
      (node (ref "U1") (pin "28") (pinfunction "VSS_28") (pintype "bidirectional"))
      (node (ref "U1") (pin "41") (pinfunction "VSS_41") (pintype "bidirectional"))
      (node (ref "U1") (pin "46") (pinfunction "VSSQ_46") (pintype "bidirectional"))
      (node (ref "U1") (pin "52") (pinfunction "VSSQ_52") (pintype "bidirectional"))
      (node (ref "U1") (pin "54") (pinfunction "VSS_54") (pintype "bidirectional"))
      (node (ref "U1") (pin "6") (pinfunction "VSSQ_6") (pintype "bidirectional"))
      (node (ref "USB_IN") (pin "5") (pinfunction "GND_5") (pintype "bidirectional"))
    )
    (net (code "6") (name "LCD_BL") (class "Default")
      (node (ref "BL_CTRL") (pin "2") (pinfunction "2_2") (pintype "passive"))
      (node (ref "BL_CTRL") (pin "4") (pinfunction "4_4") (pintype "passive"))
      (node (ref "J1") (pin "34") (pinfunction "BL_CTRL_34") (pintype "bidirectional"))
    )
    (net (code "7") (name "LED0") (class "Default")
      (node (ref "IC1") (pin "A2") (pinfunction "PE2_A2") (pintype "bidirectional"))
      (node (ref "R12") (pin "1") (pinfunction "1_1") (pintype "passive"))
    )
    (net (code "8") (name "LED1") (class "Default")
      (node (ref "IC1") (pin "A1") (pinfunction "PE3_A1") (pintype "bidirectional"))
      (node (ref "R11") (pin "1") (pinfunction "1_1") (pintype "passive"))
    )
    (net (code "9") (name "MCU_USB_N") (class "Default")
      (node (ref "IC1") (pin "C15") (pinfunction "PA11_C15") (pintype "bidirectional"))
      (node (ref "R3") (pin "1") (pinfunction "1_1") (pintype "passive"))
    )
    (net (code "10") (name "MCU_USB_P") (class "Default")
      (node (ref "IC1") (pin "B15") (pinfunction "PA12_B15") (pintype "bidirectional"))
      (node (ref "R2") (pin "1") (pinfunction "1_1") (pintype "passive"))
    )
    (net (code "11") (name "Net-(C8-Pad1)") (class "Default")
      (node (ref "C8") (pin "1") (pinfunction "1_1") (pintype "passive"))
      (node (ref "R1") (pin "1") (pinfunction "1_1") (pintype "bidirectional"))
      (node (ref "USB_IN") (pin "MH1") (pinfunction "MH1_MH1") (pintype "bidirectional"))
      (node (ref "USB_IN") (pin "MH2") (pinfunction "MH2_MH2") (pintype "bidirectional"))
      (node (ref "USB_IN") (pin "MH3") (pinfunction "MH3_MH3") (pintype "bidirectional"))
      (node (ref "USB_IN") (pin "MH4") (pinfunction "MH4_MH4") (pintype "bidirectional"))
    )
    (net (code "12") (name "Net-(D1-Pad+)") (class "Default")
      (node (ref "D1") (pin "+") (pinfunction "+_+") (pintype "passive"))
      (node (ref "R4") (pin "2") (pinfunction "2_2") (pintype "passive"))
    )
    (net (code "13") (name "Net-(D4-Pad+)") (class "Default")
      (node (ref "D4") (pin "+") (pinfunction "+_+") (pintype "passive"))
      (node (ref "R11") (pin "2") (pinfunction "2_2") (pintype "passive"))
    )
    (net (code "14") (name "Net-(D5-Pad+)") (class "Default")
      (node (ref "D5") (pin "+") (pinfunction "+_+") (pintype "passive"))
      (node (ref "R12") (pin "2") (pinfunction "2_2") (pintype "passive"))
    )
    (net (code "15") (name "Net-(IC1-PDR_ON)") (class "Default")
      (node (ref "IC1") (pin "C6") (pinfunction "PDR_ON_C6") (pintype "bidirectional"))
      (node (ref "R6") (pin "1") (pinfunction "1_1") (pintype "passive"))
    )
    (net (code "16") (name "Net-(IC2-TAB)") (class "Default")
      (node (ref "C10") (pin "1") (pinfunction "1_1") (pintype "passive"))
      (node (ref "IC2") (pin "2") (pinfunction "VOUT_2") (pintype "bidirectional"))
      (node (ref "IC2") (pin "4") (pinfunction "TAB_4") (pintype "bidirectional"))
      (node (ref "PASS_3V3") (pin "2") (pinfunction "2_2") (pintype "passive"))
      (node (ref "R4") (pin "1") (pinfunction "1_1") (pintype "passive"))
    )
    (net (code "17") (name "Net-(PROG-~{RESET})") (class "Default")
      (node (ref "PASS_RST") (pin "1") (pinfunction "1_1") (pintype "passive"))
      (node (ref "PROG") (pin "P10") (pinfunction "~{RESET}_P10") (pintype "bidirectional"))
    )
    (net (code "18") (name "PA0") (class "Default")
      (node (ref "IC1") (pin "N3") (pinfunction "PA0_N3") (pintype "bidirectional"))
      (node (ref "IO_EXT") (pin "37") (pinfunction "37_37") (pintype "passive"))
    )
    (net (code "19") (name "PA1") (class "Default")
      (node (ref "IC1") (pin "N2") (pinfunction "PA1_N2") (pintype "bidirectional"))
      (node (ref "IO_EXT") (pin "38") (pinfunction "38_38") (pintype "passive"))
    )
    (net (code "20") (name "PA2") (class "Default")
      (node (ref "IC1") (pin "P2") (pinfunction "PA2_P2") (pintype "bidirectional"))
      (node (ref "IO_EXT") (pin "35") (pinfunction "35_35") (pintype "passive"))
    )
    (net (code "21") (name "PA3") (class "Default")
      (node (ref "IC1") (pin "R2") (pinfunction "PA3_R2") (pintype "bidirectional"))
      (node (ref "IO_EXT") (pin "36") (pinfunction "36_36") (pintype "passive"))
    )
    (net (code "22") (name "PA4") (class "Default")
      (node (ref "BL_CTRL") (pin "3") (pinfunction "3_3") (pintype "passive"))
      (node (ref "IC1") (pin "N4") (pinfunction "PA4_N4") (pintype "bidirectional"))
    )
    (net (code "23") (name "PA5") (class "Default")
      (node (ref "IC1") (pin "P4") (pinfunction "PA5_P4") (pintype "bidirectional"))
      (node (ref "SPI0") (pin "2") (pinfunction "2_2") (pintype "passive"))
    )
    (net (code "24") (name "PA6") (class "Default")
      (node (ref "IC1") (pin "P3") (pinfunction "PA6_P3") (pintype "bidirectional"))
      (node (ref "SPI0") (pin "4") (pinfunction "4_4") (pintype "passive"))
    )
    (net (code "25") (name "PA7") (class "Default")
      (node (ref "IC1") (pin "R3") (pinfunction "PA7_R3") (pintype "bidirectional"))
      (node (ref "SPI0") (pin "1") (pinfunction "1_1") (pintype "passive"))
    )
    (net (code "26") (name "PA8") (class "Default")
      (node (ref "IC1") (pin "F15") (pinfunction "PA8_F15") (pintype "bidirectional"))
      (node (ref "IO_EXT") (pin "33") (pinfunction "33_33") (pintype "passive"))
    )
    (net (code "27") (name "PA9") (class "Default")
      (node (ref "IC1") (pin "E15") (pinfunction "PA9_E15") (pintype "bidirectional"))
      (node (ref "IO_EXT") (pin "34") (pinfunction "34_34") (pintype "passive"))
    )
    (net (code "28") (name "PA10") (class "Default")
      (node (ref "IC1") (pin "D15") (pinfunction "PA10_D15") (pintype "bidirectional"))
    )
    (net (code "29") (name "PA13") (class "Default")
      (node (ref "IC1") (pin "A15") (pinfunction "PA13_A15") (pintype "bidirectional"))
      (node (ref "PROG") (pin "P2") (pinfunction "SWDIO_P2") (pintype "bidirectional"))
    )
    (net (code "30") (name "PA14") (class "Default")
      (node (ref "IC1") (pin "A14") (pinfunction "PA14_A14") (pintype "bidirectional"))
      (node (ref "PROG") (pin "P4") (pinfunction "SWD_CLK_P4") (pintype "bidirectional"))
    )
    (net (code "31") (name "PA15") (class "Default")
      (node (ref "IC1") (pin "A13") (pinfunction "PA15_A13") (pintype "bidirectional"))
      (node (ref "IO_EXT") (pin "31") (pinfunction "31_31") (pintype "passive"))
    )
    (net (code "32") (name "PB0") (class "Default")
      (node (ref "IC1") (pin "R5") (pinfunction "PB0_R5") (pintype "bidirectional"))
      (node (ref "IO_EXT") (pin "32") (pinfunction "32_32") (pintype "passive"))
    )
    (net (code "33") (name "PB1") (class "Default")
      (node (ref "IC1") (pin "R4") (pinfunction "PB1_R4") (pintype "bidirectional"))
      (node (ref "IO_EXT") (pin "29") (pinfunction "29_29") (pintype "passive"))
    )
    (net (code "34") (name "PB2") (class "Default")
      (node (ref "BOOT_WHICH") (pin "2") (pinfunction "2_2") (pintype "bidirectional"))
      (node (ref "BOOT_WHICH") (pin "5") (pinfunction "5_5") (pintype "bidirectional"))
      (node (ref "IC1") (pin "M6") (pinfunction "PB2_M6") (pintype "bidirectional"))
    )
    (net (code "35") (name "PB3") (class "Default")
      (node (ref "IC1") (pin "A10") (pinfunction "PB3_A10") (pintype "bidirectional"))
      (node (ref "IO_EXT") (pin "30") (pinfunction "30_30") (pintype "passive"))
    )
    (net (code "36") (name "PB5") (class "Default")
      (node (ref "IC1") (pin "A6") (pinfunction "PB5_A6") (pintype "bidirectional"))
      (node (ref "U1") (pin "37") (pinfunction "CKE_37") (pintype "bidirectional"))
    )
    (net (code "37") (name "PB6") (class "Default")
      (node (ref "IC1") (pin "B6") (pinfunction "PB6_B6") (pintype "bidirectional"))
      (node (ref "U1") (pin "19") (pinfunction "~{CS}_19") (pintype "bidirectional"))
    )
    (net (code "38") (name "PB7") (class "Default")
      (node (ref "IC1") (pin "B5") (pinfunction "PB7_B5") (pintype "bidirectional"))
      (node (ref "IO_EXT") (pin "27") (pinfunction "27_27") (pintype "passive"))
    )
    (net (code "39") (name "PB8") (class "Default")
      (node (ref "IC1") (pin "A5") (pinfunction "PB8_A5") (pintype "bidirectional"))
      (node (ref "IO_EXT") (pin "28") (pinfunction "28_28") (pintype "passive"))
    )
    (net (code "40") (name "PB9") (class "Default")
      (node (ref "IC1") (pin "B4") (pinfunction "PB9_B4") (pintype "bidirectional"))
      (node (ref "IO_EXT") (pin "25") (pinfunction "25_25") (pintype "passive"))
    )
    (net (code "41") (name "PB10") (class "Default")
      (node (ref "IC1") (pin "R12") (pinfunction "PB10_R12") (pintype "bidirectional"))
      (node (ref "PROG") (pin "P6") (pinfunction "USART_TX_P6") (pintype "bidirectional"))
    )
    (net (code "42") (name "PB11") (class "Default")
      (node (ref "IC1") (pin "R13") (pinfunction "PB11_R13") (pintype "bidirectional"))
      (node (ref "PROG") (pin "P8") (pinfunction "USART_RX_P8") (pintype "bidirectional"))
    )
    (net (code "43") (name "PB12") (class "Default")
      (node (ref "IC1") (pin "P12") (pinfunction "PB12_P12") (pintype "bidirectional"))
      (node (ref "IO_EXT") (pin "26") (pinfunction "26_26") (pintype "passive"))
    )
    (net (code "44") (name "PB13") (class "Default")
      (node (ref "IC1") (pin "P13") (pinfunction "PB13_P13") (pintype "bidirectional"))
      (node (ref "SPI1") (pin "2") (pinfunction "2_2") (pintype "passive"))
    )
    (net (code "45") (name "PB14") (class "Default")
      (node (ref "IC1") (pin "R14") (pinfunction "PB14_R14") (pintype "bidirectional"))
      (node (ref "SPI1") (pin "4") (pinfunction "4_4") (pintype "passive"))
    )
    (net (code "46") (name "PB15") (class "Default")
      (node (ref "IC1") (pin "R15") (pinfunction "PB15_R15") (pintype "bidirectional"))
      (node (ref "SPI1") (pin "1") (pinfunction "1_1") (pintype "passive"))
    )
    (net (code "47") (name "PC0") (class "Default")
      (node (ref "IC1") (pin "M2") (pinfunction "PC0_M2") (pintype "bidirectional"))
      (node (ref "IO_EXT") (pin "23") (pinfunction "23_23") (pintype "passive"))
    )
    (net (code "48") (name "PC1") (class "Default")
      (node (ref "IC1") (pin "M3") (pinfunction "PC1_M3") (pintype "bidirectional"))
      (node (ref "IO_EXT") (pin "24") (pinfunction "24_24") (pintype "passive"))
    )
    (net (code "49") (name "PC2") (class "Default")
      (node (ref "IC1") (pin "M4") (pinfunction "PC2_M4") (pintype "bidirectional"))
      (node (ref "IO_EXT") (pin "21") (pinfunction "21_21") (pintype "passive"))
    )
    (net (code "50") (name "PC3") (class "Default")
      (node (ref "IC1") (pin "M5") (pinfunction "PC3_M5") (pintype "bidirectional"))
      (node (ref "IO_EXT") (pin "22") (pinfunction "22_22") (pintype "passive"))
    )
    (net (code "51") (name "PC4") (class "Default")
      (node (ref "IC1") (pin "N5") (pinfunction "PC4_N5") (pintype "bidirectional"))
      (node (ref "IO_EXT") (pin "17") (pinfunction "17_17") (pintype "passive"))
    )
    (net (code "52") (name "PC5") (class "Default")
      (node (ref "IC1") (pin "P5") (pinfunction "PC5_P5") (pintype "bidirectional"))
      (node (ref "IO_EXT") (pin "18") (pinfunction "18_18") (pintype "passive"))
    )
    (net (code "53") (name "PC6") (class "Default")
      (node (ref "IC1") (pin "H15") (pinfunction "PC6_H15") (pintype "bidirectional"))
      (node (ref "IO_EXT") (pin "15") (pinfunction "15_15") (pintype "passive"))
    )
    (net (code "54") (name "PC7") (class "Default")
      (node (ref "IC1") (pin "G15") (pinfunction "PC7_G15") (pintype "bidirectional"))
      (node (ref "IO_EXT") (pin "16") (pinfunction "16_16") (pintype "passive"))
    )
    (net (code "55") (name "PC8") (class "Default")
      (node (ref "IC1") (pin "G14") (pinfunction "PC8_G14") (pintype "bidirectional"))
      (node (ref "IO_EXT") (pin "13") (pinfunction "13_13") (pintype "passive"))
    )
    (net (code "56") (name "PC9") (class "Default")
      (node (ref "IC1") (pin "F14") (pinfunction "PC9_F14") (pintype "bidirectional"))
      (node (ref "IO_EXT") (pin "14") (pinfunction "14_14") (pintype "passive"))
    )
    (net (code "57") (name "PC10") (class "Default")
      (node (ref "IC1") (pin "B14") (pinfunction "PC10_B14") (pintype "bidirectional"))
      (node (ref "SPI2") (pin "2") (pinfunction "2_2") (pintype "passive"))
    )
    (net (code "58") (name "PC11") (class "Default")
      (node (ref "IC1") (pin "B13") (pinfunction "PC11_B13") (pintype "bidirectional"))
      (node (ref "SPI2") (pin "4") (pinfunction "4_4") (pintype "passive"))
    )
    (net (code "59") (name "PC12") (class "Default")
      (node (ref "IC1") (pin "A12") (pinfunction "PC12_A12") (pintype "bidirectional"))
      (node (ref "SPI2") (pin "1") (pinfunction "1_1") (pintype "passive"))
    )
    (net (code "60") (name "PC13") (class "Default")
      (node (ref "IC1") (pin "D1") (pinfunction "PC13_D1") (pintype "bidirectional"))
      (node (ref "IO_EXT") (pin "11") (pinfunction "11_11") (pintype "passive"))
    )
    (net (code "61") (name "PC14") (class "Default")
      (node (ref "IC1") (pin "E1") (pinfunction "PC14_E1") (pintype "bidirectional"))
      (node (ref "IO_EXT") (pin "12") (pinfunction "12_12") (pintype "passive"))
    )
    (net (code "62") (name "PC15") (class "Default")
      (node (ref "IC1") (pin "F1") (pinfunction "PC15_F1") (pintype "bidirectional"))
      (node (ref "IO_EXT") (pin "9") (pinfunction "9_9") (pintype "passive"))
    )
    (net (code "63") (name "PD0") (class "Default")
      (node (ref "IC1") (pin "B12") (pinfunction "PD0_B12") (pintype "bidirectional"))
      (node (ref "U1") (pin "5") (pinfunction "DQ2_5") (pintype "bidirectional"))
    )
    (net (code "64") (name "PD1") (class "Default")
      (node (ref "IC1") (pin "C12") (pinfunction "PD1_C12") (pintype "bidirectional"))
      (node (ref "U1") (pin "7") (pinfunction "DQ3_7") (pintype "bidirectional"))
    )
    (net (code "65") (name "PD2") (class "Default")
      (node (ref "IC1") (pin "D12") (pinfunction "PD2_D12") (pintype "bidirectional"))
      (node (ref "IO_EXT") (pin "10") (pinfunction "10_10") (pintype "passive"))
    )
    (net (code "66") (name "PD3") (class "Default")
      (node (ref "IC1") (pin "D11") (pinfunction "PD3_D11") (pintype "bidirectional"))
      (node (ref "IO_EXT") (pin "7") (pinfunction "7_7") (pintype "passive"))
    )
    (net (code "67") (name "PD4") (class "Default")
      (node (ref "IC1") (pin "D10") (pinfunction "PD4_D10") (pintype "bidirectional"))
      (node (ref "IO_EXT") (pin "8") (pinfunction "8_8") (pintype "passive"))
    )
    (net (code "68") (name "PD5") (class "Default")
      (node (ref "IC1") (pin "C11") (pinfunction "PD5_C11") (pintype "bidirectional"))
      (node (ref "U1") (pin "16") (pinfunction "~{WE}_16") (pintype "bidirectional"))
    )
    (net (code "69") (name "PD6") (class "Default")
      (node (ref "IC1") (pin "B11") (pinfunction "PD6_B11") (pintype "bidirectional"))
      (node (ref "IO_EXT") (pin "5") (pinfunction "5_5") (pintype "passive"))
    )
    (net (code "70") (name "PD7") (class "Default")
      (node (ref "IC1") (pin "A11") (pinfunction "PD7_A11") (pintype "bidirectional"))
      (node (ref "IO_EXT") (pin "6") (pinfunction "6_6") (pintype "passive"))
    )
    (net (code "71") (name "PD8") (class "Default")
      (node (ref "IC1") (pin "P15") (pinfunction "PD8_P15") (pintype "bidirectional"))
      (node (ref "U1") (pin "50") (pinfunction "DQ13_50") (pintype "bidirectional"))
    )
    (net (code "72") (name "PD9") (class "Default")
      (node (ref "IC1") (pin "P14") (pinfunction "PD9_P14") (pintype "bidirectional"))
      (node (ref "U1") (pin "51") (pinfunction "DQ14_51") (pintype "bidirectional"))
    )
    (net (code "73") (name "PD10") (class "Default")
      (node (ref "IC1") (pin "N15") (pinfunction "PD10_N15") (pintype "bidirectional"))
      (node (ref "U1") (pin "53") (pinfunction "DQ15_53") (pintype "bidirectional"))
    )
    (net (code "74") (name "PD11") (class "Default")
      (node (ref "IC1") (pin "N14") (pinfunction "PD11_N14") (pintype "bidirectional"))
      (node (ref "IO_EXT") (pin "3") (pinfunction "3_3") (pintype "passive"))
    )
    (net (code "75") (name "PD12") (class "Default")
      (node (ref "IC1") (pin "N13") (pinfunction "PD12_N13") (pintype "bidirectional"))
      (node (ref "IO_EXT") (pin "4") (pinfunction "4_4") (pintype "passive"))
    )
    (net (code "76") (name "PD14") (class "Default")
      (node (ref "IC1") (pin "M14") (pinfunction "PD14_M14") (pintype "bidirectional"))
      (node (ref "U1") (pin "2") (pinfunction "DQ0_2") (pintype "bidirectional"))
    )
    (net (code "77") (name "PD15") (class "Default")
      (node (ref "IC1") (pin "L14") (pinfunction "PD15_L14") (pintype "bidirectional"))
      (node (ref "U1") (pin "4") (pinfunction "DQ1_4") (pintype "bidirectional"))
    )
    (net (code "78") (name "PE0") (class "Default")
      (node (ref "IC1") (pin "A4") (pinfunction "PE0_A4") (pintype "bidirectional"))
      (node (ref "U1") (pin "15") (pinfunction "LDQM_15") (pintype "bidirectional"))
    )
    (net (code "79") (name "PE1") (class "Default")
      (node (ref "IC1") (pin "A3") (pinfunction "PE1_A3") (pintype "bidirectional"))
      (node (ref "U1") (pin "39") (pinfunction "UDQM_39") (pintype "bidirectional"))
    )
    (net (code "80") (name "PE4") (class "Default")
      (node (ref "IC1") (pin "B1") (pinfunction "PE4_B1") (pintype "bidirectional"))
      (node (ref "J1") (pin "21") (pinfunction "B0_21") (pintype "bidirectional"))
    )
    (net (code "81") (name "PE5") (class "Default")
      (node (ref "IC1") (pin "B2") (pinfunction "PE5_B2") (pintype "bidirectional"))
      (node (ref "J1") (pin "12") (pinfunction "G0_12") (pintype "bidirectional"))
    )
    (net (code "82") (name "PE6") (class "Default")
      (node (ref "IC1") (pin "B3") (pinfunction "PE6_B3") (pintype "bidirectional"))
      (node (ref "J1") (pin "13") (pinfunction "G1_13") (pintype "bidirectional"))
    )
    (net (code "83") (name "PE7") (class "Default")
      (node (ref "IC1") (pin "R8") (pinfunction "PE7_R8") (pintype "bidirectional"))
      (node (ref "U1") (pin "8") (pinfunction "DQ4_8") (pintype "bidirectional"))
    )
    (net (code "84") (name "PE8") (class "Default")
      (node (ref "IC1") (pin "P8") (pinfunction "PE8_P8") (pintype "bidirectional"))
      (node (ref "U1") (pin "10") (pinfunction "DQ5_10") (pintype "bidirectional"))
    )
    (net (code "85") (name "PE9") (class "Default")
      (node (ref "IC1") (pin "P9") (pinfunction "PE9_P9") (pintype "bidirectional"))
      (node (ref "U1") (pin "11") (pinfunction "DQ6_11") (pintype "bidirectional"))
    )
    (net (code "86") (name "PE10") (class "Default")
      (node (ref "IC1") (pin "R9") (pinfunction "PE10_R9") (pintype "bidirectional"))
      (node (ref "U1") (pin "13") (pinfunction "DQ7_13") (pintype "bidirectional"))
    )
    (net (code "87") (name "PE11") (class "Default")
      (node (ref "IC1") (pin "P10") (pinfunction "PE11_P10") (pintype "bidirectional"))
      (node (ref "U1") (pin "42") (pinfunction "DQ8_42") (pintype "bidirectional"))
    )
    (net (code "88") (name "PE12") (class "Default")
      (node (ref "IC1") (pin "R10") (pinfunction "PE12_R10") (pintype "bidirectional"))
      (node (ref "U1") (pin "44") (pinfunction "DQ9_44") (pintype "bidirectional"))
    )
    (net (code "89") (name "PE13") (class "Default")
      (node (ref "IC1") (pin "N11") (pinfunction "PE13_N11") (pintype "bidirectional"))
      (node (ref "U1") (pin "45") (pinfunction "DQ10_45") (pintype "bidirectional"))
    )
    (net (code "90") (name "PE14") (class "Default")
      (node (ref "IC1") (pin "P11") (pinfunction "PE14_P11") (pintype "bidirectional"))
      (node (ref "U1") (pin "47") (pinfunction "DQ11_47") (pintype "bidirectional"))
    )
    (net (code "91") (name "PE15") (class "Default")
      (node (ref "IC1") (pin "R11") (pinfunction "PE15_R11") (pintype "bidirectional"))
      (node (ref "U1") (pin "48") (pinfunction "DQ12_48") (pintype "bidirectional"))
    )
    (net (code "92") (name "PF0") (class "Default")
      (node (ref "IC1") (pin "E2") (pinfunction "PF0_E2") (pintype "bidirectional"))
      (node (ref "U1") (pin "23") (pinfunction "A0_23") (pintype "bidirectional"))
    )
    (net (code "93") (name "PF1") (class "Default")
      (node (ref "IC1") (pin "H3") (pinfunction "PF1_H3") (pintype "bidirectional"))
      (node (ref "U1") (pin "24") (pinfunction "A1_24") (pintype "bidirectional"))
    )
    (net (code "94") (name "PF2") (class "Default")
      (node (ref "IC1") (pin "H2") (pinfunction "PF2_H2") (pintype "bidirectional"))
      (node (ref "U1") (pin "25") (pinfunction "A2_25") (pintype "bidirectional"))
    )
    (net (code "95") (name "PF3") (class "Default")
      (node (ref "IC1") (pin "J2") (pinfunction "PF3_J2") (pintype "bidirectional"))
      (node (ref "U1") (pin "26") (pinfunction "A3_26") (pintype "bidirectional"))
    )
    (net (code "96") (name "PF4") (class "Default")
      (node (ref "IC1") (pin "J3") (pinfunction "PF4_J3") (pintype "bidirectional"))
      (node (ref "U1") (pin "29") (pinfunction "A4_29") (pintype "bidirectional"))
    )
    (net (code "97") (name "PF5") (class "Default")
      (node (ref "IC1") (pin "K3") (pinfunction "PF5_K3") (pintype "bidirectional"))
      (node (ref "U1") (pin "30") (pinfunction "A5_30") (pintype "bidirectional"))
    )
    (net (code "98") (name "PF6") (class "Default")
      (node (ref "IC1") (pin "K2") (pinfunction "PF6_K2") (pintype "bidirectional"))
      (node (ref "J1") (pin "35") (pinfunction "TP_CS_35") (pintype "bidirectional"))
    )
    (net (code "99") (name "PF7") (class "Default")
      (node (ref "IC1") (pin "K1") (pinfunction "PF7_K1") (pintype "bidirectional"))
      (node (ref "J1") (pin "38") (pinfunction "TP_CLK_38") (pintype "bidirectional"))
    )
    (net (code "100") (name "PF8") (class "Default")
      (node (ref "IC1") (pin "L3") (pinfunction "PF8_L3") (pintype "bidirectional"))
      (node (ref "J1") (pin "37") (pinfunction "TP_MISO_37") (pintype "bidirectional"))
    )
    (net (code "101") (name "PF9") (class "Default")
      (node (ref "IC1") (pin "L2") (pinfunction "PF9_L2") (pintype "bidirectional"))
      (node (ref "J1") (pin "36") (pinfunction "TP_MOSI_36") (pintype "bidirectional"))
    )
    (net (code "102") (name "PF10") (class "Default")
      (node (ref "IC1") (pin "L1") (pinfunction "PF10_L1") (pintype "bidirectional"))
      (node (ref "J1") (pin "33") (pinfunction "DE_33") (pintype "bidirectional"))
    )
    (net (code "103") (name "PF11") (class "Default")
      (node (ref "IC1") (pin "R6") (pinfunction "PF11_R6") (pintype "bidirectional"))
      (node (ref "U1") (pin "18") (pinfunction "~{RAS}_18") (pintype "bidirectional"))
    )
    (net (code "104") (name "PF12") (class "Default")
      (node (ref "IC1") (pin "P6") (pinfunction "PF12_P6") (pintype "bidirectional"))
      (node (ref "U1") (pin "31") (pinfunction "A6_31") (pintype "bidirectional"))
    )
    (net (code "105") (name "PF13") (class "Default")
      (node (ref "IC1") (pin "N6") (pinfunction "PF13_N6") (pintype "bidirectional"))
      (node (ref "U1") (pin "32") (pinfunction "A7_32") (pintype "bidirectional"))
    )
    (net (code "106") (name "PF14") (class "Default")
      (node (ref "IC1") (pin "R7") (pinfunction "PF14_R7") (pintype "bidirectional"))
      (node (ref "U1") (pin "33") (pinfunction "A8_33") (pintype "bidirectional"))
    )
    (net (code "107") (name "PF15") (class "Default")
      (node (ref "IC1") (pin "P7") (pinfunction "PF15_P7") (pintype "bidirectional"))
      (node (ref "U1") (pin "34") (pinfunction "A9_34") (pintype "bidirectional"))
    )
    (net (code "108") (name "PG0") (class "Default")
      (node (ref "IC1") (pin "N7") (pinfunction "PG0_N7") (pintype "bidirectional"))
      (node (ref "U1") (pin "22") (pinfunction "A10/AP_22") (pintype "bidirectional"))
    )
    (net (code "109") (name "PG1") (class "Default")
      (node (ref "IC1") (pin "M7") (pinfunction "PG1_M7") (pintype "bidirectional"))
      (node (ref "U1") (pin "35") (pinfunction "A11_35") (pintype "bidirectional"))
    )
    (net (code "110") (name "PG2") (class "Default")
      (node (ref "IC1") (pin "L15") (pinfunction "PG2_L15") (pintype "bidirectional"))
      (node (ref "U1") (pin "36") (pinfunction "A12_36") (pintype "bidirectional"))
    )
    (net (code "111") (name "PG4") (class "Default")
      (node (ref "IC1") (pin "K14") (pinfunction "PG4_K14") (pintype "bidirectional"))
      (node (ref "U1") (pin "20") (pinfunction "BS0_20") (pintype "bidirectional"))
    )
    (net (code "112") (name "PG5") (class "Default")
      (node (ref "IC1") (pin "K13") (pinfunction "PG5_K13") (pintype "bidirectional"))
      (node (ref "U1") (pin "21") (pinfunction "BS1_21") (pintype "bidirectional"))
    )
    (net (code "113") (name "PG6") (class "Default")
      (node (ref "IC1") (pin "J15") (pinfunction "PG6_J15") (pintype "bidirectional"))
      (node (ref "J1") (pin "10") (pinfunction "R7_10") (pintype "bidirectional"))
    )
    (net (code "114") (name "PG7") (class "Default")
      (node (ref "IC1") (pin "J14") (pinfunction "PG7_J14") (pintype "bidirectional"))
      (node (ref "J1") (pin "30") (pinfunction "PCLK_30") (pintype "bidirectional"))
    )
    (net (code "115") (name "PG8") (class "Default")
      (node (ref "IC1") (pin "H14") (pinfunction "PG8_H14") (pintype "bidirectional"))
      (node (ref "U1") (pin "38") (pinfunction "CLK_38") (pintype "bidirectional"))
    )
    (net (code "116") (name "PG10") (class "Default")
      (node (ref "IC1") (pin "B10") (pinfunction "PG10_B10") (pintype "bidirectional"))
      (node (ref "J1") (pin "23") (pinfunction "B2_23") (pintype "bidirectional"))
    )
    (net (code "117") (name "PG11") (class "Default")
      (node (ref "IC1") (pin "B9") (pinfunction "PG11_B9") (pintype "bidirectional"))
      (node (ref "J1") (pin "24") (pinfunction "B3_24") (pintype "bidirectional"))
    )
    (net (code "118") (name "PG12") (class "Default")
      (node (ref "IC1") (pin "B8") (pinfunction "PG12_B8") (pintype "bidirectional"))
      (node (ref "J1") (pin "22") (pinfunction "B1_22") (pintype "bidirectional"))
    )
    (net (code "119") (name "PG15") (class "Default")
      (node (ref "IC1") (pin "B7") (pinfunction "PG15_B7") (pintype "bidirectional"))
      (node (ref "U1") (pin "17") (pinfunction "~{CAS}_17") (pintype "bidirectional"))
    )
    (net (code "120") (name "PH0") (class "Default")
      (node (ref "C12") (pin "1") (pinfunction "1_1") (pintype "passive"))
      (node (ref "IC1") (pin "G1") (pinfunction "PH0_G1") (pintype "bidirectional"))
      (node (ref "Q2") (pin "1") (pinfunction "X1_1") (pintype "bidirectional"))
    )
    (net (code "121") (name "PH1") (class "Default")
      (node (ref "C13") (pin "1") (pinfunction "1_1") (pintype "passive"))
      (node (ref "IC1") (pin "H1") (pinfunction "PH1_H1") (pintype "bidirectional"))
      (node (ref "Q2") (pin "3") (pinfunction "X2_3") (pintype "bidirectional"))
    )
    (net (code "122") (name "PH2") (class "Default")
      (node (ref "IC1") (pin "F4") (pinfunction "PH2_F4") (pintype "bidirectional"))
      (node (ref "J1") (pin "3") (pinfunction "R0_3") (pintype "bidirectional"))
    )
    (net (code "123") (name "PH3") (class "Default")
      (node (ref "IC1") (pin "G4") (pinfunction "PH3_G4") (pintype "bidirectional"))
      (node (ref "J1") (pin "4") (pinfunction "R1_4") (pintype "bidirectional"))
    )
    (net (code "124") (name "PH4") (class "Default")
      (node (ref "I2C1") (pin "2") (pinfunction "2_2") (pintype "passive"))
      (node (ref "IC1") (pin "H4") (pinfunction "PH4_H4") (pintype "bidirectional"))
      (node (ref "R8") (pin "1") (pinfunction "1_1") (pintype "passive"))
    )
    (net (code "125") (name "PH5") (class "Default")
      (node (ref "I2C1") (pin "4") (pinfunction "4_4") (pintype "passive"))
      (node (ref "IC1") (pin "J4") (pinfunction "PH5_J4") (pintype "bidirectional"))
      (node (ref "R37") (pin "1") (pinfunction "1_1") (pintype "passive"))
    )
    (net (code "126") (name "PH8") (class "Default")
      (node (ref "IC1") (pin "M12") (pinfunction "PH8_M12") (pintype "bidirectional"))
      (node (ref "J1") (pin "5") (pinfunction "R2_5") (pintype "bidirectional"))
    )
    (net (code "127") (name "PH9") (class "Default")
      (node (ref "IC1") (pin "M13") (pinfunction "PH9_M13") (pintype "bidirectional"))
      (node (ref "J1") (pin "6") (pinfunction "R3_6") (pintype "bidirectional"))
    )
    (net (code "128") (name "PH10") (class "Default")
      (node (ref "IC1") (pin "L13") (pinfunction "PH10_L13") (pintype "bidirectional"))
      (node (ref "J1") (pin "7") (pinfunction "R4_7") (pintype "bidirectional"))
    )
    (net (code "129") (name "PH11") (class "Default")
      (node (ref "IC1") (pin "L12") (pinfunction "PH11_L12") (pintype "bidirectional"))
      (node (ref "J1") (pin "8") (pinfunction "R5_8") (pintype "bidirectional"))
    )
    (net (code "130") (name "PH12") (class "Default")
      (node (ref "IC1") (pin "K12") (pinfunction "PH12_K12") (pintype "bidirectional"))
      (node (ref "J1") (pin "9") (pinfunction "R6_9") (pintype "bidirectional"))
    )
    (net (code "131") (name "PH13") (class "Default")
      (node (ref "IC1") (pin "E12") (pinfunction "PH13_E12") (pintype "bidirectional"))
      (node (ref "J1") (pin "14") (pinfunction "G2_14") (pintype "bidirectional"))
    )
    (net (code "132") (name "PH14") (class "Default")
      (node (ref "IC1") (pin "E13") (pinfunction "PH14_E13") (pintype "bidirectional"))
      (node (ref "J1") (pin "15") (pinfunction "G3_15") (pintype "bidirectional"))
    )
    (net (code "133") (name "PH15") (class "Default")
      (node (ref "IC1") (pin "D13") (pinfunction "PH15_D13") (pintype "bidirectional"))
      (node (ref "J1") (pin "16") (pinfunction "G4_16") (pintype "bidirectional"))
    )
    (net (code "134") (name "PI0") (class "Default")
      (node (ref "IC1") (pin "E14") (pinfunction "PI0_E14") (pintype "bidirectional"))
      (node (ref "J1") (pin "17") (pinfunction "G5_17") (pintype "bidirectional"))
    )
    (net (code "135") (name "PI1") (class "Default")
      (node (ref "IC1") (pin "D14") (pinfunction "PI1_D14") (pintype "bidirectional"))
      (node (ref "J1") (pin "18") (pinfunction "G6_18") (pintype "bidirectional"))
    )
    (net (code "136") (name "PI2") (class "Default")
      (node (ref "IC1") (pin "C14") (pinfunction "PI2_C14") (pintype "bidirectional"))
      (node (ref "J1") (pin "19") (pinfunction "G7_19") (pintype "bidirectional"))
    )
    (net (code "137") (name "PI3") (class "Default")
      (node (ref "IC1") (pin "C13") (pinfunction "PI3_C13") (pintype "bidirectional"))
      (node (ref "J1") (pin "40") (pinfunction "~{RST}_40") (pintype "bidirectional"))
    )
    (net (code "138") (name "PI4") (class "Default")
      (node (ref "IC1") (pin "D4") (pinfunction "PI4_D4") (pintype "bidirectional"))
      (node (ref "J1") (pin "25") (pinfunction "B4_25") (pintype "bidirectional"))
    )
    (net (code "139") (name "PI5") (class "Default")
      (node (ref "IC1") (pin "C4") (pinfunction "PI5_C4") (pintype "bidirectional"))
      (node (ref "J1") (pin "26") (pinfunction "B5_26") (pintype "bidirectional"))
    )
    (net (code "140") (name "PI6") (class "Default")
      (node (ref "IC1") (pin "C3") (pinfunction "PI6_C3") (pintype "bidirectional"))
      (node (ref "J1") (pin "27") (pinfunction "B6_27") (pintype "bidirectional"))
    )
    (net (code "141") (name "PI7") (class "Default")
      (node (ref "IC1") (pin "C2") (pinfunction "PI7_C2") (pintype "bidirectional"))
      (node (ref "J1") (pin "28") (pinfunction "B7_28") (pintype "bidirectional"))
    )
    (net (code "142") (name "PI8") (class "Default")
      (node (ref "IC1") (pin "D2") (pinfunction "PI8_D2") (pintype "bidirectional"))
      (node (ref "J1") (pin "39") (pinfunction "TP_IRQ_39") (pintype "bidirectional"))
    )
    (net (code "143") (name "PI9") (class "Default")
      (node (ref "IC1") (pin "D3") (pinfunction "PI9_D3") (pintype "bidirectional"))
      (node (ref "J1") (pin "32") (pinfunction "VSYNC_32") (pintype "bidirectional"))
    )
    (net (code "144") (name "PI10") (class "Default")
      (node (ref "IC1") (pin "E3") (pinfunction "PI10_E3") (pintype "bidirectional"))
      (node (ref "J1") (pin "31") (pinfunction "HSYNC_31") (pintype "bidirectional"))
    )
    (net (code "145") (name "USB_N") (class "Default")
      (node (ref "R3") (pin "2") (pinfunction "2_2") (pintype "passive"))
      (node (ref "USB_IN") (pin "2") (pinfunction "D-_2") (pintype "bidirectional"))
    )
    (net (code "146") (name "USB_P") (class "Default")
      (node (ref "R2") (pin "2") (pinfunction "2_2") (pintype "passive"))
      (node (ref "USB_IN") (pin "3") (pinfunction "D+_3") (pintype "bidirectional"))
    )
    (net (code "147") (name "V+") (class "Default")
      (node (ref "+5V_IN") (pin "+") (pinfunction "+_+") (pintype "bidirectional"))
      (node (ref "POWER") (pin "1") (pinfunction "1_1") (pintype "bidirectional"))
      (node (ref "POWER") (pin "6") (pinfunction "6_6") (pintype "bidirectional"))
    )
    (net (code "148") (name "unconnected-(IC1-NC-PadF13)") (class "Default")
      (node (ref "IC1") (pin "F13") (pinfunction "NC_F13") (pintype "no_connect"))
    )
    (net (code "149") (name "unconnected-(IC1-NC-PadL4)") (class "Default")
      (node (ref "IC1") (pin "L4") (pinfunction "NC_L4") (pintype "no_connect"))
    )
    (net (code "150") (name "unconnected-(IC1-NC-PadM10)") (class "Default")
      (node (ref "IC1") (pin "M10") (pinfunction "NC_M10") (pintype "no_connect"))
    )
    (net (code "151") (name "unconnected-(IC1-PB4-PadA9)") (class "Default")
      (node (ref "IC1") (pin "A9") (pinfunction "PB4_A9") (pintype "bidirectional"))
    )
    (net (code "152") (name "unconnected-(IC1-PD13-PadM15)") (class "Default")
      (node (ref "IC1") (pin "M15") (pinfunction "PD13_M15") (pintype "bidirectional"))
    )
    (net (code "153") (name "unconnected-(IC1-PG3-PadK15)") (class "Default")
      (node (ref "IC1") (pin "K15") (pinfunction "PG3_K15") (pintype "bidirectional"))
    )
    (net (code "154") (name "unconnected-(IC1-PG9-PadC10)") (class "Default")
      (node (ref "IC1") (pin "C10") (pinfunction "PG9_C10") (pintype "bidirectional"))
    )
    (net (code "155") (name "unconnected-(IC1-PG13-PadA8)") (class "Default")
      (node (ref "IC1") (pin "A8") (pinfunction "PG13_A8") (pintype "bidirectional"))
    )
    (net (code "156") (name "unconnected-(IC1-PG14-PadA7)") (class "Default")
      (node (ref "IC1") (pin "A7") (pinfunction "PG14_A7") (pintype "bidirectional"))
    )
    (net (code "157") (name "unconnected-(IC1-PH6-PadM11)") (class "Default")
      (node (ref "IC1") (pin "M11") (pinfunction "PH6_M11") (pintype "bidirectional"))
    )
    (net (code "158") (name "unconnected-(IC1-PH7-PadN12)") (class "Default")
      (node (ref "IC1") (pin "N12") (pinfunction "PH7_N12") (pintype "bidirectional"))
    )
    (net (code "159") (name "unconnected-(IC1-PI11-PadE4)") (class "Default")
      (node (ref "IC1") (pin "E4") (pinfunction "PI11_E4") (pintype "bidirectional"))
    )
    (net (code "160") (name "unconnected-(PROG-NC-PadP7)") (class "Default")
      (node (ref "PROG") (pin "P7") (pinfunction "NC_P7") (pintype "bidirectional"))
    )
    (net (code "161") (name "unconnected-(U1-NC-Pad40)") (class "Default")
      (node (ref "U1") (pin "40") (pinfunction "NC_40") (pintype "no_connect"))
    )
    (net (code "162") (name "unconnected-(USB_IN-ID-Pad4)") (class "Default")
      (node (ref "USB_IN") (pin "4") (pinfunction "ID_4") (pintype "bidirectional"))
    )
    (net (code "163") (name "unconnected-(USB_IN-VBUS-Pad1)") (class "Default")
      (node (ref "USB_IN") (pin "1") (pinfunction "VBUS_1") (pintype "bidirectional"))
    )
    (net (code "164") (name "~{RST}") (class "Default")
      (node (ref "IC1") (pin "J1") (pinfunction "~{RST}_J1") (pintype "bidirectional"))
      (node (ref "PASS_RST") (pin "2") (pinfunction "2_2") (pintype "passive"))
      (node (ref "R7") (pin "1") (pinfunction "1_1") (pintype "passive"))
      (node (ref "RESET") (pin "3") (pinfunction "3_3") (pintype "passive"))
      (node (ref "RESET") (pin "4") (pinfunction "4_4") (pintype "passive"))
    )
  )
)
